# EMC03-Motion_Control.net
KiCad netlist of a schematic drawn in EAGLE
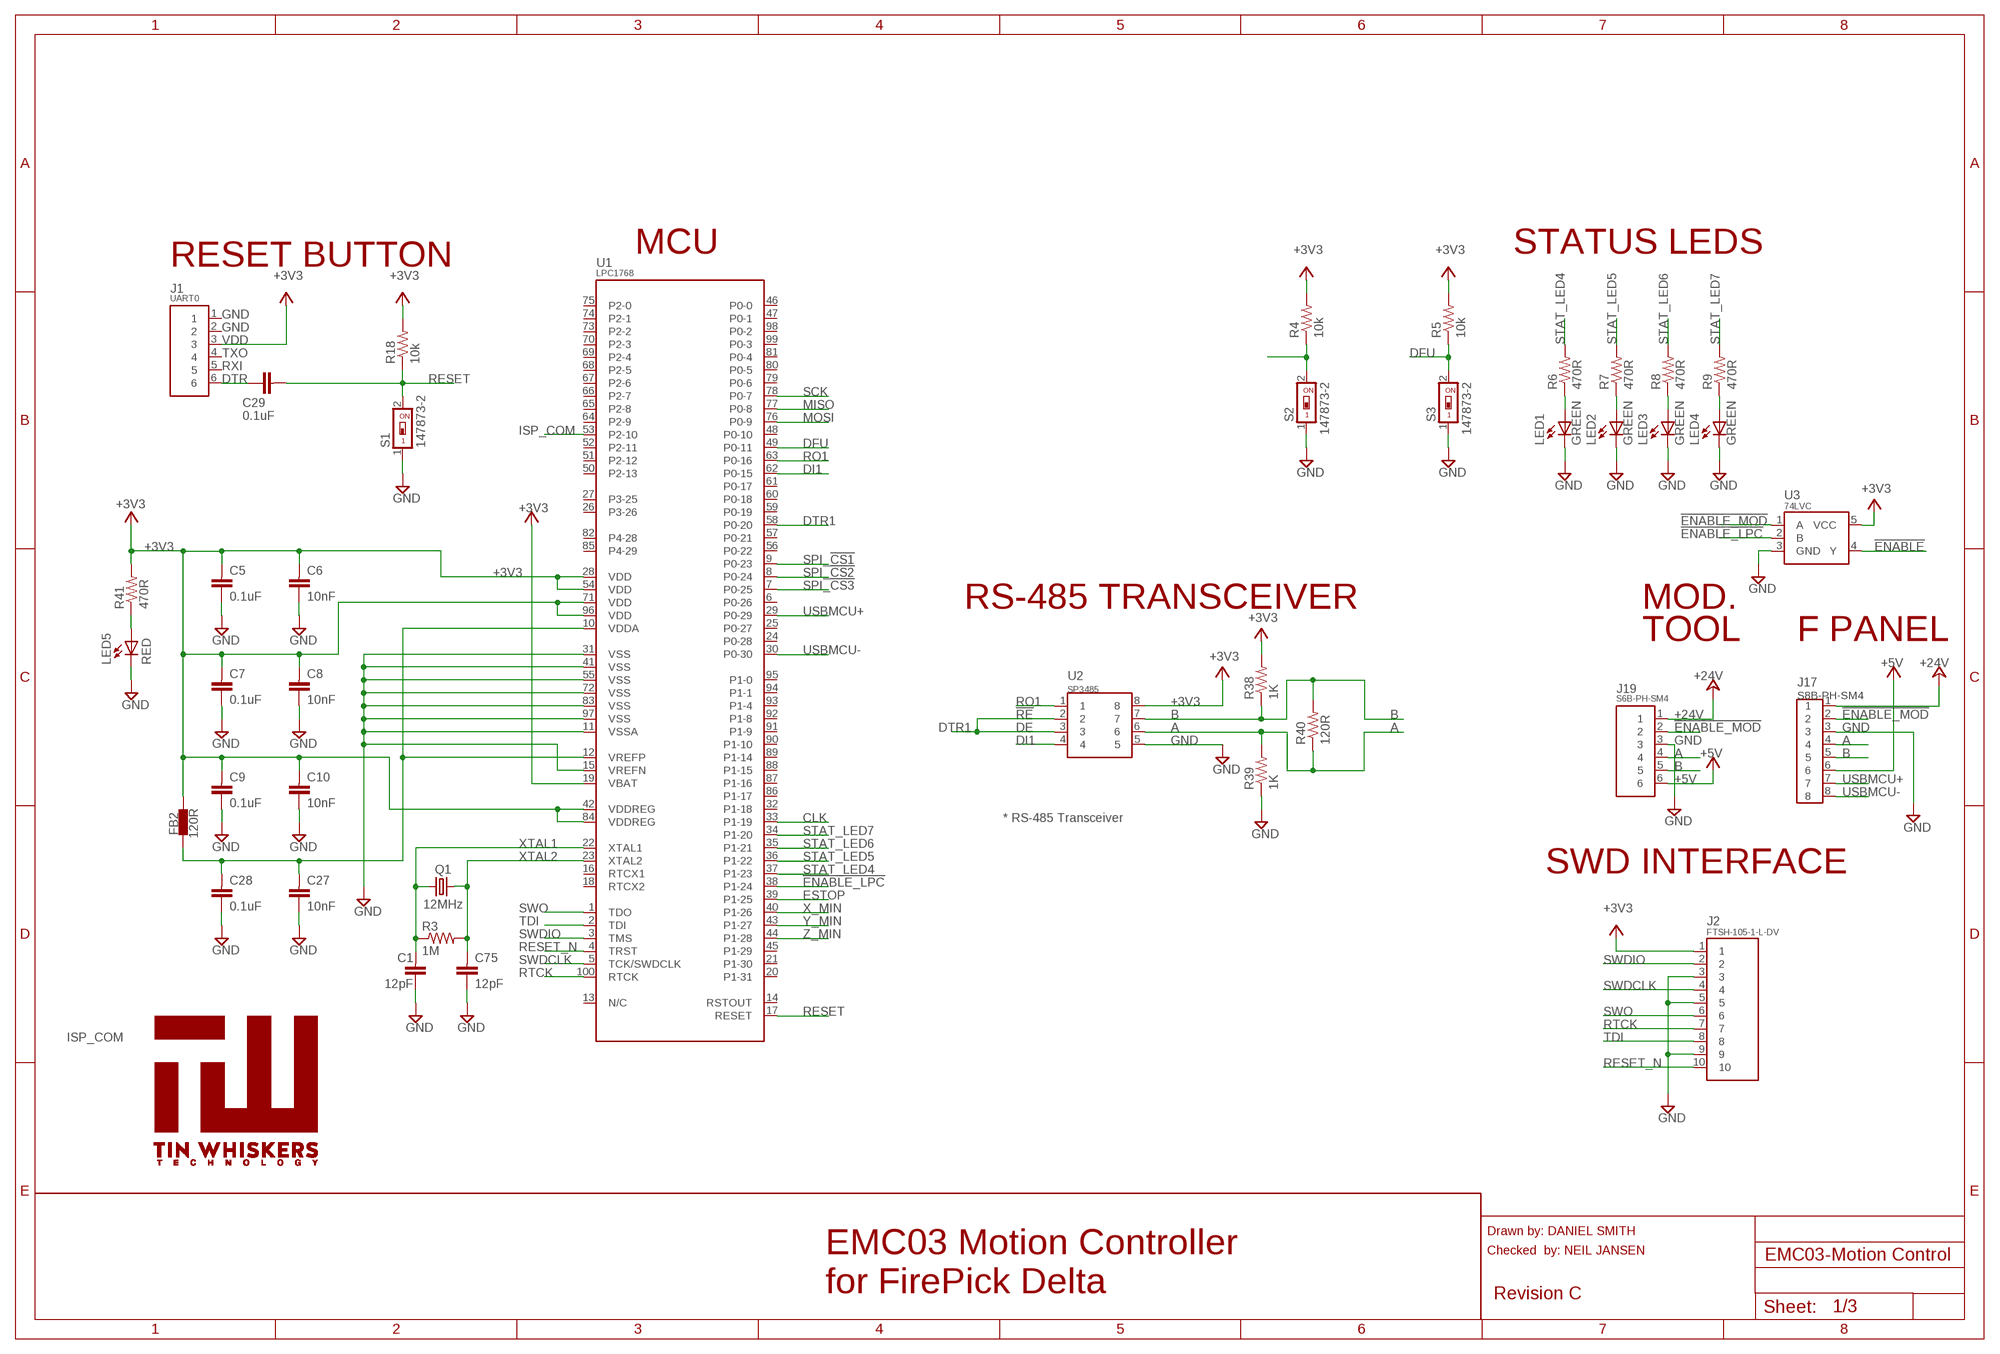
[diagram p0: schematic, sheet 1]
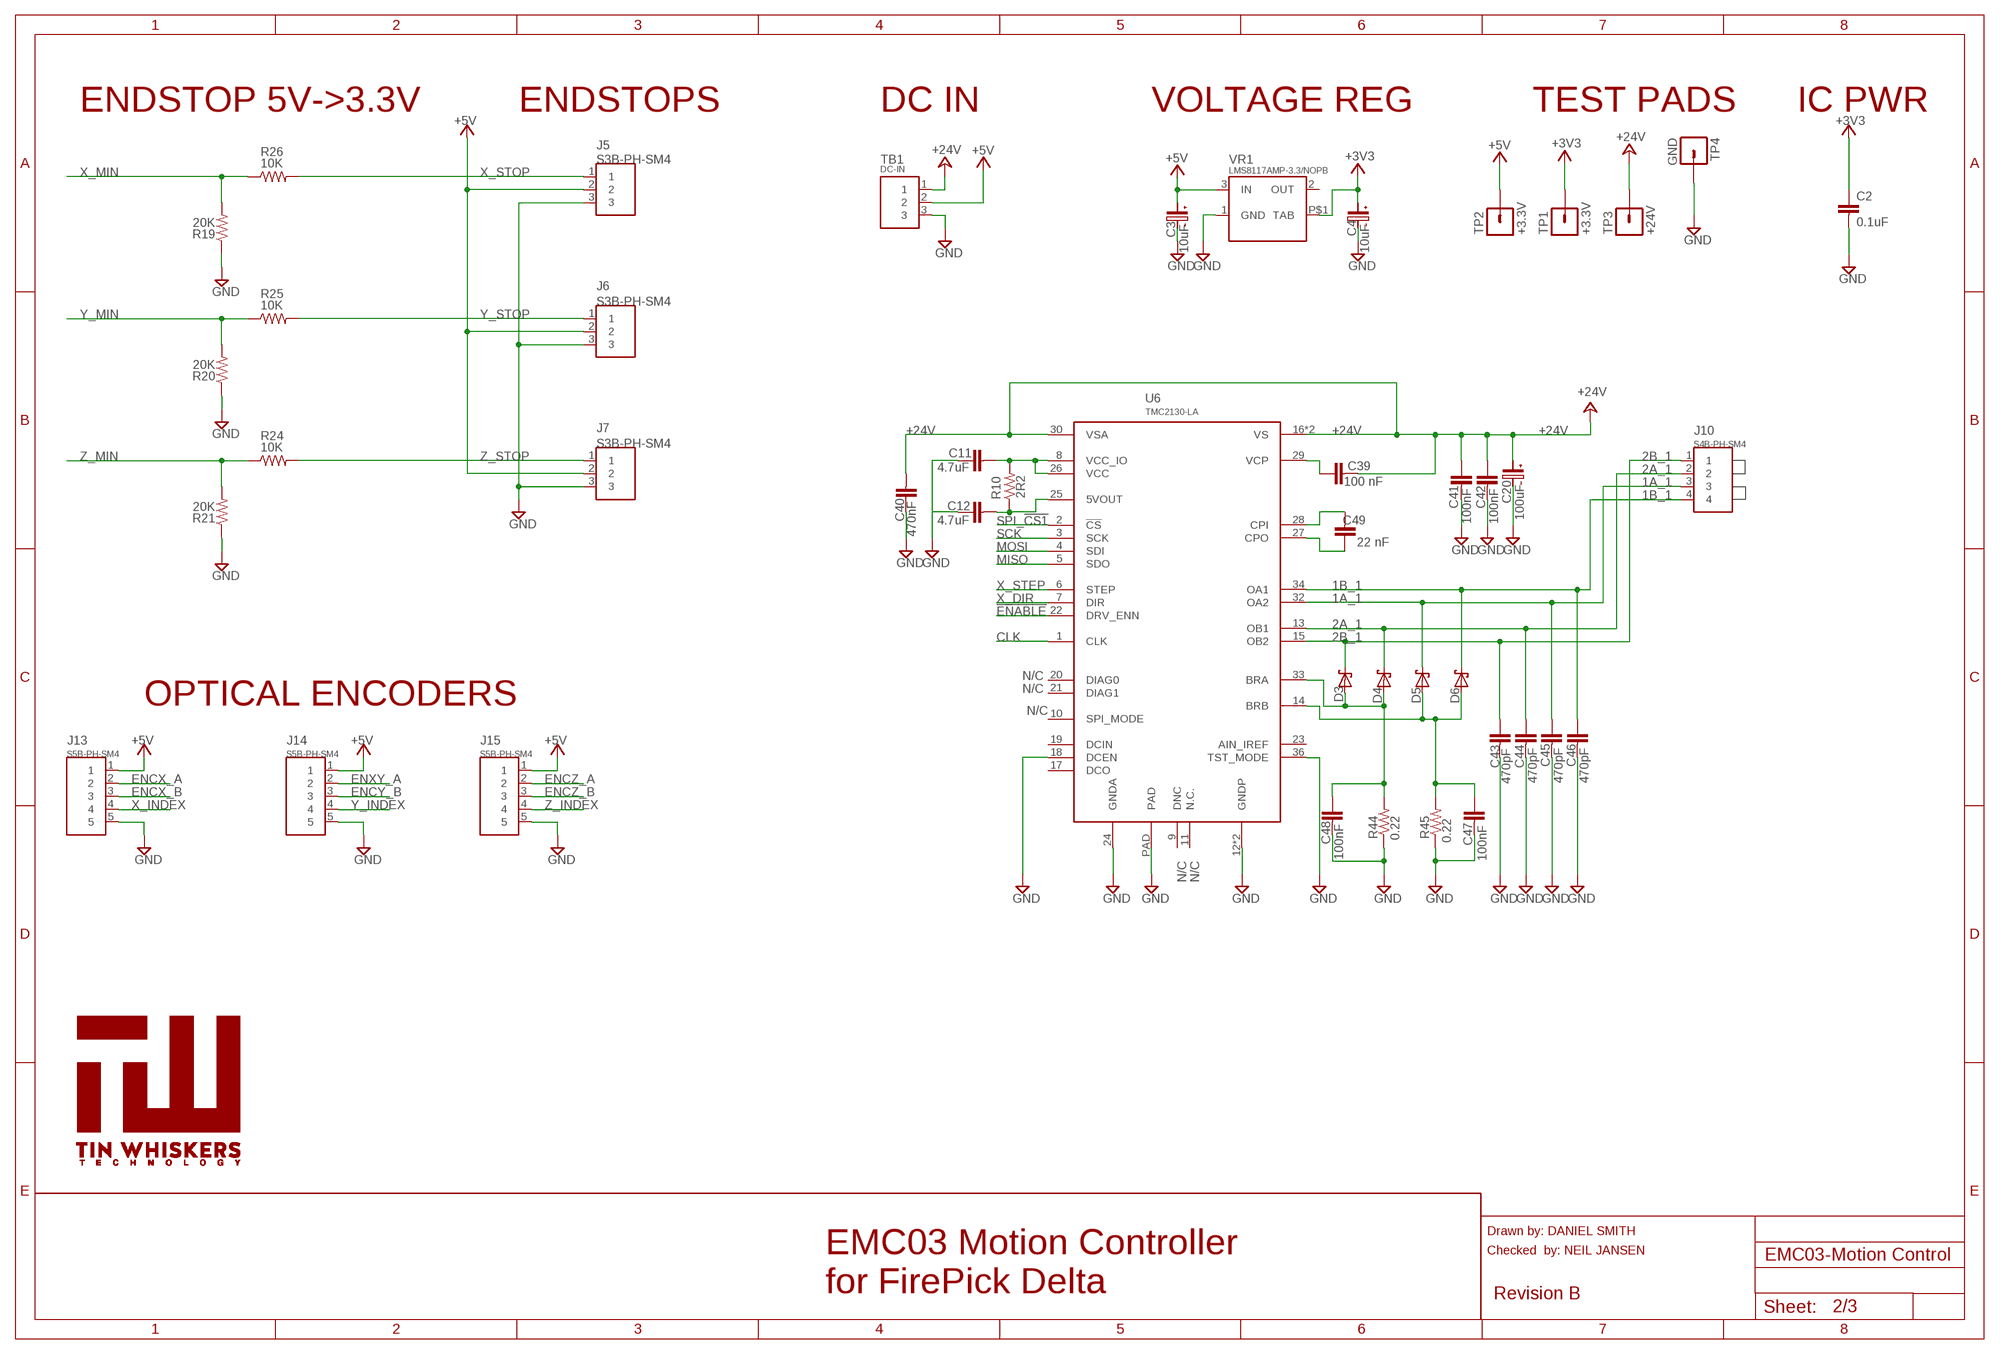
[diagram p1: schematic, sheet 2]
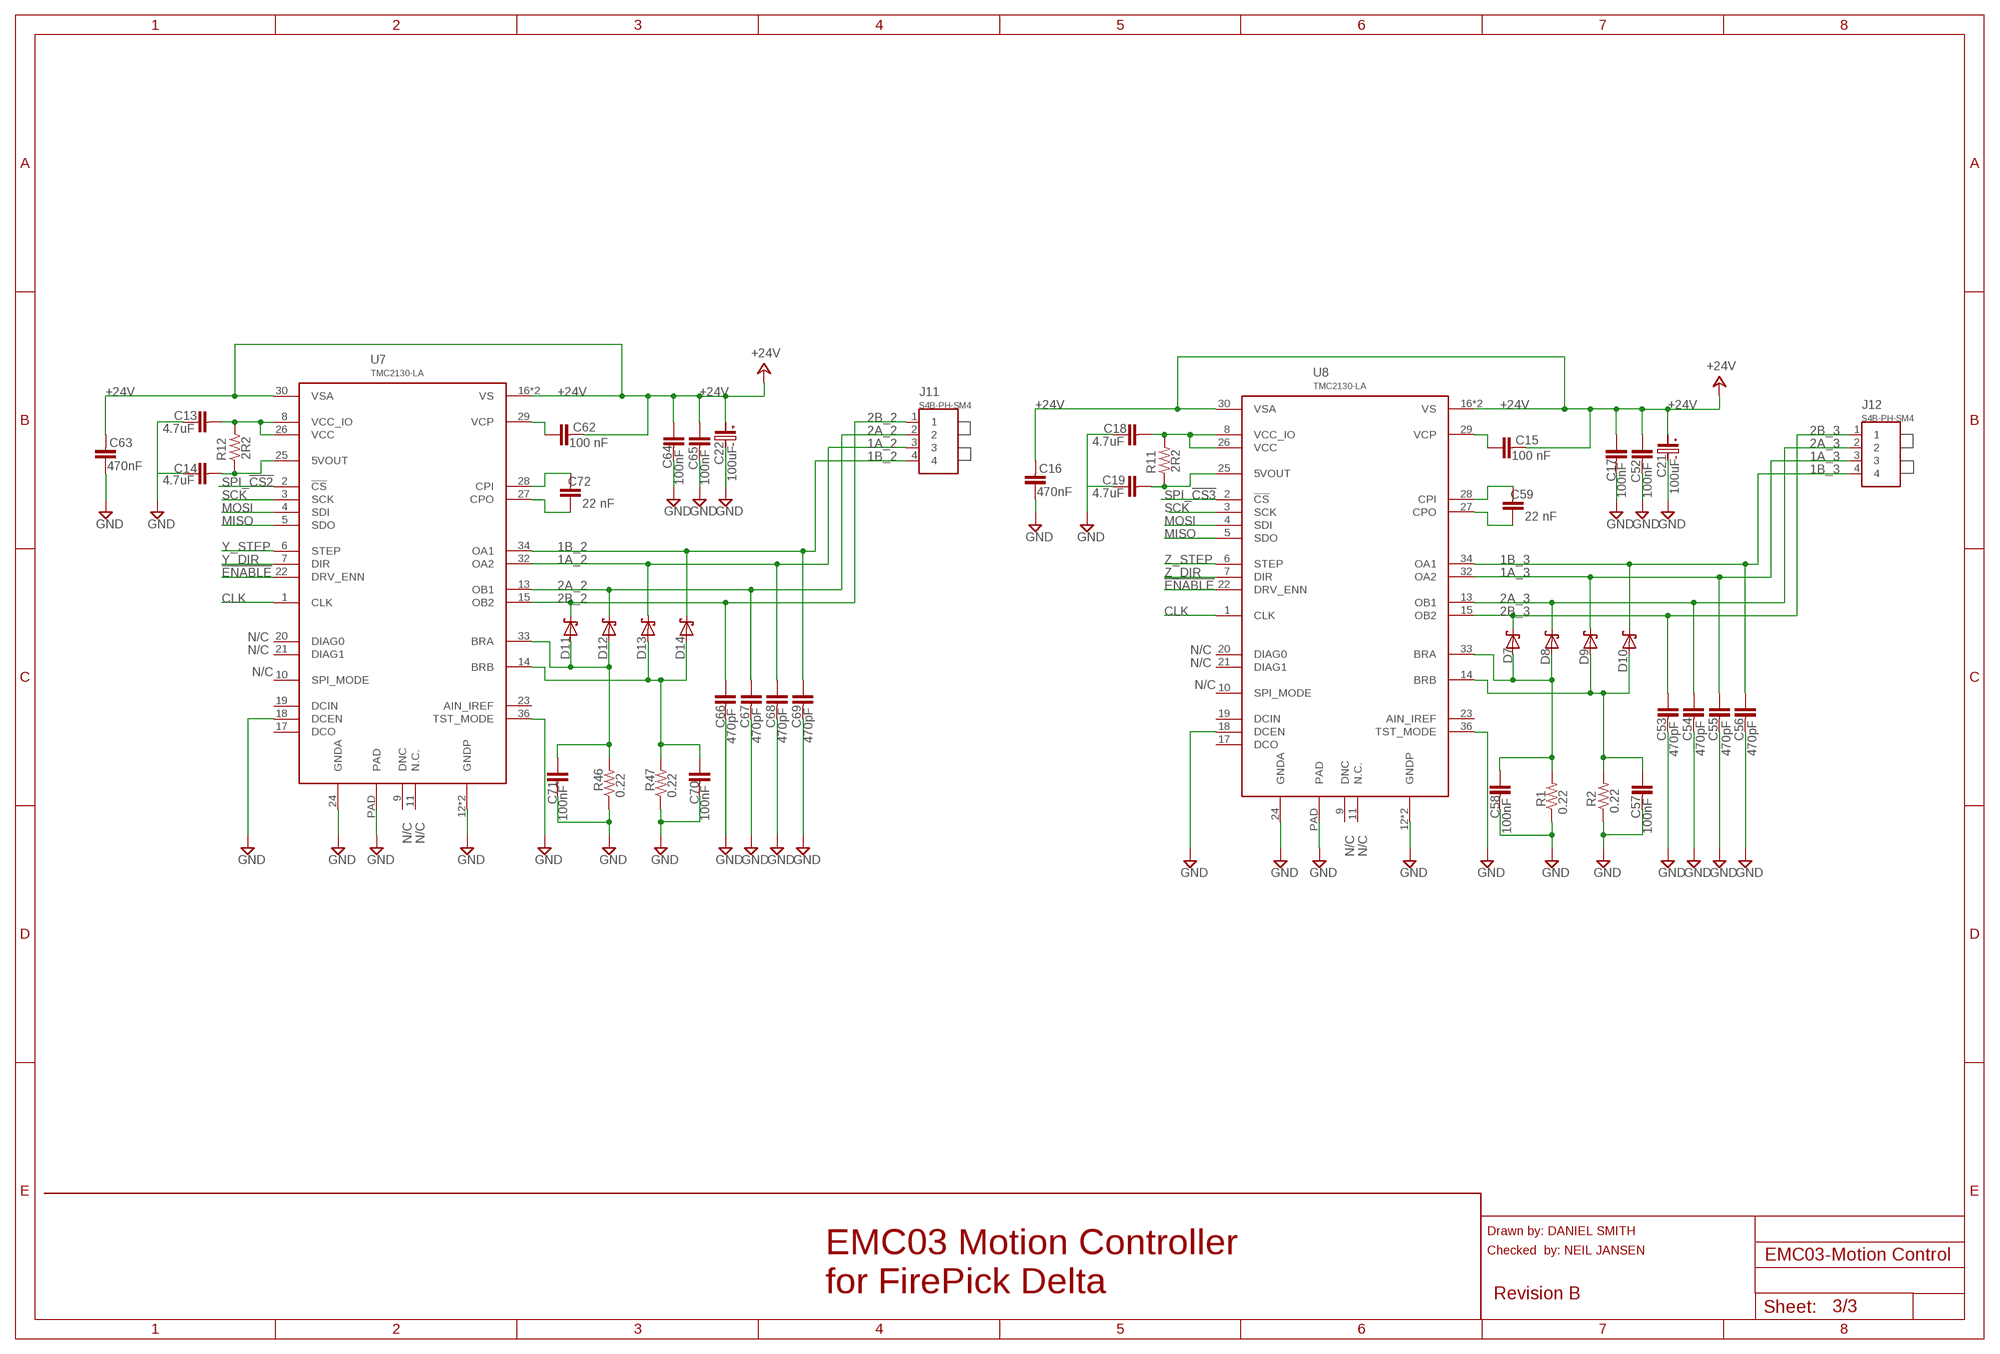
[diagram p2: schematic, sheet 3]

(export (version "E")
  (design (tool "Eeschema 10.0.6"))
  (components
    (comp (ref "C1")
      (value "12pF")
      (footprint "eagle-import:C0603")
      (fields (field (name "PARTNO") "GRM1885C1H120FA01J"))
      (libsource (lib "eagle-import") (part "CPL-CAP-C0G-0603-12PF-50V"))
    )
    (comp (ref "C5")
      (value "0.1uF")
      (footprint "eagle-import:C0603")
      (fields (field (name "PARTNO") "GMK107BJ104KAHT"))
      (libsource (lib "eagle-import") (part "CPL-CAP-X5R-0603-0.1UF-35V"))
    )
    (comp (ref "C6")
      (value "10nF")
      (footprint "eagle-import:C0603")
      (fields (field (name "PARTNO") "GRM188R71H103KA01D"))
      (libsource (lib "eagle-import") (part "CPL-CAP-X7R-10NF-16V"))
    )
    (comp (ref "C7")
      (value "0.1uF")
      (footprint "eagle-import:C0603")
      (fields (field (name "PARTNO") "GMK107BJ104KAHT"))
      (libsource (lib "eagle-import") (part "CPL-CAP-X5R-0603-0.1UF-35V"))
    )
    (comp (ref "C8")
      (value "10nF")
      (footprint "eagle-import:C0603")
      (fields (field (name "PARTNO") "GRM188R71H103KA01D"))
      (libsource (lib "eagle-import") (part "CPL-CAP-X7R-10NF-16V"))
    )
    (comp (ref "C9")
      (value "0.1uF")
      (footprint "eagle-import:C0603")
      (fields (field (name "PARTNO") "GMK107BJ104KAHT"))
      (libsource (lib "eagle-import") (part "CPL-CAP-X5R-0603-0.1UF-35V"))
    )
    (comp (ref "C10")
      (value "10nF")
      (footprint "eagle-import:C0603")
      (fields (field (name "PARTNO") "GRM188R71H103KA01D"))
      (libsource (lib "eagle-import") (part "CPL-CAP-X7R-10NF-16V"))
    )
    (comp (ref "C27")
      (value "10nF")
      (footprint "eagle-import:C0603")
      (fields (field (name "PARTNO") "GRM188R71H103KA01D"))
      (libsource (lib "eagle-import") (part "CPL-CAP-X7R-10NF-16V"))
    )
    (comp (ref "C28")
      (value "0.1uF")
      (footprint "eagle-import:C0603")
      (fields (field (name "PARTNO") "GMK107BJ104KAHT"))
      (libsource (lib "eagle-import") (part "CPL-CAP-X5R-0603-0.1UF-35V"))
    )
    (comp (ref "C29")
      (value "0.1uF")
      (footprint "eagle-import:C0603")
      (fields (field (name "PARTNO") "GMK107BJ104KAHT"))
      (libsource (lib "eagle-import") (part "CPL-CAP-X7R-0603-0.1UF-35V"))
    )
    (comp (ref "C75")
      (value "12pF")
      (footprint "eagle-import:C0603")
      (fields (field (name "PARTNO") "GRM1885C1H120FA01J"))
      (libsource (lib "eagle-import") (part "CPL-CAP-C0G-0603-12PF-50V"))
    )
    (comp (ref "FB2")
      (value "120R")
      (footprint "eagle-import:F0603")
      (fields (field (name "PARTNO") "BLM18AG121SN1D"))
      (libsource (lib "eagle-import") (part "CPL-IND-FER-120OHM-2A"))
    )
    (comp (ref "J1")
      (value "UART0")
      (footprint "eagle-import:CON-HDR-6POS-MALE")
      (fields (field (name "PARTNO") "67996-206HLF"))
      (libsource (lib "eagle-import") (part "CPL-CON-HEADER-0.1IN-6P-M"))
    )
    (comp (ref "J2")
      (value "FTSH-105-1-L-DV")
      (footprint "eagle-import:FTSH-105-01-XXX-DV-K")
      (fields (field (name "PARTNO") "FTSH-105-01-L-DV"))
      (libsource (lib "eagle-import") (part "CPL-CON-HEADER-0.05IN-10P-M"))
    )
    (comp (ref "J17")
      (value "S8B-PH-SM4")
      (footprint "eagle-import:CONN-JST-PH-2.0MM-8P-SMT-RA")
      (fields (field (name "PARTNO") "S8B-PH-SM4-TB(LF)(SN)"))
      (libsource (lib "eagle-import") (part "CPL-CON-JST-2.0MM-8P-M-RA"))
    )
    (comp (ref "J19")
      (value "S6B-PH-SM4")
      (footprint "eagle-import:CONN-JST-PH-2.0MM-6P-SMT-RA")
      (fields (field (name "PARTNO") "S6B-PH-SM4-TB(LF)(SN)"))
      (libsource (lib "eagle-import") (part "CPL-CON-JST-2.0MM-6P-M-RA"))
    )
    (comp (ref "LED1")
      (value "GREEN")
      (footprint "eagle-import:LED0603")
      (fields (field (name "PARTNO") "SML-D12M8WT86"))
      (libsource (lib "eagle-import") (part "CPL-LED-0603-GREEN"))
    )
    (comp (ref "LED2")
      (value "GREEN")
      (footprint "eagle-import:LED0603")
      (fields (field (name "PARTNO") "SML-D12M8WT86"))
      (libsource (lib "eagle-import") (part "CPL-LED-0603-GREEN"))
    )
    (comp (ref "LED3")
      (value "GREEN")
      (footprint "eagle-import:LED0603")
      (fields (field (name "PARTNO") "SML-D12M8WT86"))
      (libsource (lib "eagle-import") (part "CPL-LED-0603-GREEN"))
    )
    (comp (ref "LED4")
      (value "GREEN")
      (footprint "eagle-import:LED0603")
      (fields (field (name "PARTNO") "SML-D12M8WT86"))
      (libsource (lib "eagle-import") (part "CPL-LED-0603-GREEN"))
    )
    (comp (ref "LED5")
      (value "RED")
      (footprint "eagle-import:LED0603")
      (fields (field (name "PARTNO") "SML-D12U8WT86"))
      (libsource (lib "eagle-import") (part "CPL-LED-0603-RED"))
    )
    (comp (ref "Q1")
      (value "12MHz")
      (footprint "eagle-import:HC-49_U-S")
      (fields (field (name "PARTNO") "HCM4912000000ABJT"))
      (libsource (lib "eagle-import") (part "CPL-OSC-CRY-12MHZ-18PF"))
    )
    (comp (ref "R3")
      (value "1M")
      (footprint "eagle-import:R0603")
      (fields (field (name "PARTNO") "RC0603FR-071ML"))
      (libsource (lib "eagle-import") (part "CPL-RES-0603-1M-0.1W"))
    )
    (comp (ref "R4")
      (value "10k")
      (footprint "eagle-import:R0603")
      (fields (field (name "PARTNO") "RC0603FR-0710KL"))
      (libsource (lib "eagle-import") (part "CPL-RES-0603-10K-0.1W"))
    )
    (comp (ref "R5")
      (value "10k")
      (footprint "eagle-import:R0603")
      (fields (field (name "PARTNO") "RC0603FR-0710KL"))
      (libsource (lib "eagle-import") (part "CPL-RES-0603-10K-0.1W"))
    )
    (comp (ref "R6")
      (value "470R")
      (footprint "eagle-import:R0603")
      (fields (field (name "PARTNO") "RC0603FR-07470RL"))
      (libsource (lib "eagle-import") (part "CPL-RES-0603-470R-0.1W"))
    )
    (comp (ref "R7")
      (value "470R")
      (footprint "eagle-import:R0603")
      (fields (field (name "PARTNO") "RC0603FR-07470RL"))
      (libsource (lib "eagle-import") (part "CPL-RES-0603-470R-0.1W"))
    )
    (comp (ref "R8")
      (value "470R")
      (footprint "eagle-import:R0603")
      (fields (field (name "PARTNO") "RC0603FR-07470RL"))
      (libsource (lib "eagle-import") (part "CPL-RES-0603-470R-0.1W"))
    )
    (comp (ref "R9")
      (value "470R")
      (footprint "eagle-import:R0603")
      (fields (field (name "PARTNO") "RC0603FR-07470RL"))
      (libsource (lib "eagle-import") (part "CPL-RES-0603-470R-0.1W"))
    )
    (comp (ref "R18")
      (value "10k")
      (footprint "eagle-import:R0603")
      (fields (field (name "PARTNO") "RC0603FR-0710KL"))
      (libsource (lib "eagle-import") (part "CPL-RES-0603-10K-0.1W"))
    )
    (comp (ref "R38")
      (value "1K")
      (footprint "eagle-import:R0603")
      (fields (field (name "PARTNO") "RC0603FR-071KL"))
      (libsource (lib "eagle-import") (part "CPL-RES-0603-1K-0.1W"))
    )
    (comp (ref "R39")
      (value "1K")
      (footprint "eagle-import:R0603")
      (fields (field (name "PARTNO") "RC0603FR-071KL"))
      (libsource (lib "eagle-import") (part "CPL-RES-0603-1K-0.1W"))
    )
    (comp (ref "R40")
      (value "120R")
      (footprint "eagle-import:R0603")
      (fields (field (name "PARTNO") "RC0805FR-07120RL"))
      (libsource (lib "eagle-import") (part "CPL-RES-0603-120-0.1W"))
    )
    (comp (ref "R41")
      (value "470R")
      (footprint "eagle-import:R0603")
      (fields (field (name "PARTNO") "RC0603FR-07470RL"))
      (libsource (lib "eagle-import") (part "CPL-RES-0603-470R-0.1W"))
    )
    (comp (ref "S1")
      (value "147873-2")
      (footprint "eagle-import:147873-2")
      (libsource (lib "eagle-import") (part "CPL-SW-MOM-147873-2"))
    )
    (comp (ref "S2")
      (value "147873-2")
      (footprint "eagle-import:147873-2")
      (libsource (lib "eagle-import") (part "CPL-SW-MOM-147873-2"))
    )
    (comp (ref "S3")
      (value "147873-2")
      (footprint "eagle-import:147873-2")
      (libsource (lib "eagle-import") (part "CPL-SW-MOM-147873-2"))
    )
    (comp (ref "U$1")
      (value "TIN-WHISKERSSMALL")
      (footprint "eagle-import:TIN-WHISKERS-SMALL")
      (libsource (lib "eagle-import") (part "TIN-WHISKERSSMALL"))
    )
    (comp (ref "U1")
      (value "LPC1768")
      (footprint "eagle-import:100-LQFP")
      (libsource (lib "eagle-import") (part "LPC1768LQFP-100"))
    )
    (comp (ref "U2")
      (value "SP3485")
      (footprint "eagle-import:SOICN-8")
      (libsource (lib "eagle-import") (part "SP3485"))
    )
    (comp (ref "U3")
      (value "74LVC")
      (footprint "eagle-import:SOT-23-5")
      (fields (field (name "PARTNO") "SN74LVC1G32DBVR"))
      (libsource (lib "eagle-import") (part "CPL-IC-LOGIC-OR-1CH-74LVC"))
    )
    (comp (ref "C13")
      (value "4.7uF")
      (footprint "eagle-import:C0603")
      (fields (field (name "PARTNO") "GRM188C81E475KE11D"))
      (libsource (lib "eagle-import") (part "CPL-CAP-X5R-0603-4.7UF-10V"))
    )
    (comp (ref "C14")
      (value "4.7uF")
      (footprint "eagle-import:C0603")
      (fields (field (name "PARTNO") "GRM188C81E475KE11D"))
      (libsource (lib "eagle-import") (part "CPL-CAP-X5R-0603-4.7UF-10V"))
    )
    (comp (ref "C15")
      (value "100 nF")
      (footprint "eagle-import:C0603")
      (fields (field (name "PARTNO") "UMK107B7104KA-T"))
      (libsource (lib "eagle-import") (part "CPL-CAP-X7R-0603-100NF-100V"))
    )
    (comp (ref "C16")
      (value "470nF")
      (footprint "eagle-import:C0603")
      (fields (field (name "PARTNO") "UMK107B7474KA-TR"))
      (libsource (lib "eagle-import") (part "CPL-CAP-X7R-0603-0.47UF-35V"))
    )
    (comp (ref "C17")
      (value "100nF")
      (footprint "eagle-import:C0603")
      (fields (field (name "PARTNO") "UMK107B7104KA-T"))
      (libsource (lib "eagle-import") (part "CPL-CAP-X7R-0603-100NF-100V"))
    )
    (comp (ref "C18")
      (value "4.7uF")
      (footprint "eagle-import:C0603")
      (fields (field (name "PARTNO") "GRM188C81E475KE11D"))
      (libsource (lib "eagle-import") (part "CPL-CAP-X5R-0603-4.7UF-10V"))
    )
    (comp (ref "C19")
      (value "4.7uF")
      (footprint "eagle-import:C0603")
      (fields (field (name "PARTNO") "GRM188C81E475KE11D"))
      (libsource (lib "eagle-import") (part "CPL-CAP-X5R-0603-4.7UF-10V"))
    )
    (comp (ref "C21")
      (value "100uF")
      (footprint "eagle-import:C-SMD-6.3MM")
      (fields (field (name "PARTNO") "EEE-FTH101XAP"))
      (libsource (lib "eagle-import") (part "CPL-CAP-ALU-SMD-100UF-50V"))
    )
    (comp (ref "C22")
      (value "100uF")
      (footprint "eagle-import:C-SMD-6.3MM")
      (fields (field (name "PARTNO") "EEE-FTH101XAP"))
      (libsource (lib "eagle-import") (part "CPL-CAP-ALU-SMD-100UF-50V"))
    )
    (comp (ref "C52")
      (value "100nF")
      (footprint "eagle-import:C0603")
      (fields (field (name "PARTNO") "UMK107B7104KA-T"))
      (libsource (lib "eagle-import") (part "CPL-CAP-X7R-0603-100NF-100V"))
    )
    (comp (ref "C53")
      (value "470pF")
      (footprint "eagle-import:C0603")
      (fields (field (name "PARTNO") "GRM188R72A471KA01D"))
      (libsource (lib "eagle-import") (part "CPL-CAP-X7R-0603-470PF-100V"))
    )
    (comp (ref "C54")
      (value "470pF")
      (footprint "eagle-import:C0603")
      (fields (field (name "PARTNO") "GRM188R72A471KA01D"))
      (libsource (lib "eagle-import") (part "CPL-CAP-X7R-0603-470PF-100V"))
    )
    (comp (ref "C55")
      (value "470pF")
      (footprint "eagle-import:C0603")
      (fields (field (name "PARTNO") "GRM188R72A471KA01D"))
      (libsource (lib "eagle-import") (part "CPL-CAP-X7R-0603-470PF-100V"))
    )
    (comp (ref "C56")
      (value "470pF")
      (footprint "eagle-import:C0603")
      (fields (field (name "PARTNO") "GRM188R72A471KA01D"))
      (libsource (lib "eagle-import") (part "CPL-CAP-X7R-0603-470PF-100V"))
    )
    (comp (ref "C57")
      (value "100nF")
      (footprint "eagle-import:C0603")
      (fields (field (name "PARTNO") "UMK107B7104KA-T"))
      (libsource (lib "eagle-import") (part "CPL-CAP-X7R-0603-100NF-50V"))
    )
    (comp (ref "C58")
      (value "100nF")
      (footprint "eagle-import:C0603")
      (fields (field (name "PARTNO") "UMK107B7104KA-T"))
      (libsource (lib "eagle-import") (part "CPL-CAP-X7R-0603-100NF-50V"))
    )
    (comp (ref "C59")
      (value "22 nF")
      (footprint "eagle-import:C0603")
      (fields (field (name "PARTNO") "GRM188R71H223KA01D"))
      (libsource (lib "eagle-import") (part "CPL-CAP-X7R-0603-22NF-50V{dblquote}"))
    )
    (comp (ref "C62")
      (value "100 nF")
      (footprint "eagle-import:C0603")
      (fields (field (name "PARTNO") "UMK107B7104KA-T"))
      (libsource (lib "eagle-import") (part "CPL-CAP-X7R-0603-100NF-100V"))
    )
    (comp (ref "C63")
      (value "470nF")
      (footprint "eagle-import:C0603")
      (fields (field (name "PARTNO") "UMK107B7474KA-TR"))
      (libsource (lib "eagle-import") (part "CPL-CAP-X7R-0603-0.47UF-35V"))
    )
    (comp (ref "C64")
      (value "100nF")
      (footprint "eagle-import:C0603")
      (fields (field (name "PARTNO") "UMK107B7104KA-T"))
      (libsource (lib "eagle-import") (part "CPL-CAP-X7R-0603-100NF-100V"))
    )
    (comp (ref "C65")
      (value "100nF")
      (footprint "eagle-import:C0603")
      (fields (field (name "PARTNO") "UMK107B7104KA-T"))
      (libsource (lib "eagle-import") (part "CPL-CAP-X7R-0603-100NF-100V"))
    )
    (comp (ref "C66")
      (value "470pF")
      (footprint "eagle-import:C0603")
      (fields (field (name "PARTNO") "GRM188R72A471KA01D"))
      (libsource (lib "eagle-import") (part "CPL-CAP-X7R-0603-470PF-100V"))
    )
    (comp (ref "C67")
      (value "470pF")
      (footprint "eagle-import:C0603")
      (fields (field (name "PARTNO") "GRM188R72A471KA01D"))
      (libsource (lib "eagle-import") (part "CPL-CAP-X7R-0603-470PF-100V"))
    )
    (comp (ref "C68")
      (value "470pF")
      (footprint "eagle-import:C0603")
      (fields (field (name "PARTNO") "GRM188R72A471KA01D"))
      (libsource (lib "eagle-import") (part "CPL-CAP-X7R-0603-470PF-100V"))
    )
    (comp (ref "C69")
      (value "470pF")
      (footprint "eagle-import:C0603")
      (fields (field (name "PARTNO") "GRM188R72A471KA01D"))
      (libsource (lib "eagle-import") (part "CPL-CAP-X7R-0603-470PF-100V"))
    )
    (comp (ref "C70")
      (value "100nF")
      (footprint "eagle-import:C0603")
      (fields (field (name "PARTNO") "UMK107B7104KA-T"))
      (libsource (lib "eagle-import") (part "CPL-CAP-X7R-0603-100NF-50V"))
    )
    (comp (ref "C71")
      (value "100nF")
      (footprint "eagle-import:C0603")
      (fields (field (name "PARTNO") "UMK107B7104KA-T"))
      (libsource (lib "eagle-import") (part "CPL-CAP-X7R-0603-100NF-50V"))
    )
    (comp (ref "C72")
      (value "22 nF")
      (footprint "eagle-import:C0603")
      (fields (field (name "PARTNO") "GRM188R71H223KA01D"))
      (libsource (lib "eagle-import") (part "CPL-CAP-X7R-0603-22NF-50V{dblquote}"))
    )
    (comp (ref "D7")
      (value "MSS1P6")
      (footprint "eagle-import:MICRO-SMP")
      (libsource (lib "eagle-import") (part "CPL-DIO-MSS1P6-MICROSMP"))
    )
    (comp (ref "D8")
      (value "MSS1P6")
      (footprint "eagle-import:MICRO-SMP")
      (libsource (lib "eagle-import") (part "CPL-DIO-MSS1P6-MICROSMP"))
    )
    (comp (ref "D9")
      (value "MSS1P6")
      (footprint "eagle-import:MICRO-SMP")
      (libsource (lib "eagle-import") (part "CPL-DIO-MSS1P6-MICROSMP"))
    )
    (comp (ref "D10")
      (value "MSS1P6")
      (footprint "eagle-import:MICRO-SMP")
      (libsource (lib "eagle-import") (part "CPL-DIO-MSS1P6-MICROSMP"))
    )
    (comp (ref "D11")
      (value "MSS1P6")
      (footprint "eagle-import:MICRO-SMP")
      (libsource (lib "eagle-import") (part "CPL-DIO-MSS1P6-MICROSMP"))
    )
    (comp (ref "D12")
      (value "MSS1P6")
      (footprint "eagle-import:MICRO-SMP")
      (libsource (lib "eagle-import") (part "CPL-DIO-MSS1P6-MICROSMP"))
    )
    (comp (ref "D13")
      (value "MSS1P6")
      (footprint "eagle-import:MICRO-SMP")
      (libsource (lib "eagle-import") (part "CPL-DIO-MSS1P6-MICROSMP"))
    )
    (comp (ref "D14")
      (value "MSS1P6")
      (footprint "eagle-import:MICRO-SMP")
      (libsource (lib "eagle-import") (part "CPL-DIO-MSS1P6-MICROSMP"))
    )
    (comp (ref "J11")
      (value "S4B-PH-SM4")
      (footprint "eagle-import:CONN-JST-PH-2.0MM-4P-SMT-RA")
      (fields (field (name "PARTNO") "S4B-PH-SM4-TB(LF)(SN)"))
      (libsource (lib "eagle-import") (part "CPL-CON-JST-2.0MM-4P-M-RA"))
    )
    (comp (ref "J12")
      (value "S4B-PH-SM4")
      (footprint "eagle-import:CONN-JST-PH-2.0MM-4P-SMT-RA")
      (fields (field (name "PARTNO") "S4B-PH-SM4-TB(LF)(SN)"))
      (libsource (lib "eagle-import") (part "CPL-CON-JST-2.0MM-4P-M-RA"))
    )
    (comp (ref "R1")
      (value "0.22")
      (footprint "eagle-import:R1206")
      (fields (field (name "PARTNO") "RL1206FR-7W0R22L"))
      (libsource (lib "eagle-import") (part "CPL-RES-1206-0.22-0.5W"))
    )
    (comp (ref "R2")
      (value "0.22")
      (footprint "eagle-import:R1206")
      (fields (field (name "PARTNO") "RL1206FR-7W0R22L"))
      (libsource (lib "eagle-import") (part "CPL-RES-1206-0.22-0.5W"))
    )
    (comp (ref "R11")
      (value "2R2")
      (footprint "eagle-import:R0603")
      (fields (field (name "PARTNO") "RC0603FR-072R2L"))
      (libsource (lib "eagle-import") (part "CPL-RES-0603-2.2-0.1W"))
    )
    (comp (ref "R12")
      (value "2R2")
      (footprint "eagle-import:R0603")
      (fields (field (name "PARTNO") "RC0603FR-072R2L"))
      (libsource (lib "eagle-import") (part "CPL-RES-0603-2.2-0.1W"))
    )
    (comp (ref "R46")
      (value "0.22")
      (footprint "eagle-import:R1206")
      (fields (field (name "PARTNO") "RL1206FR-7W0R22L"))
      (libsource (lib "eagle-import") (part "CPL-RES-1206-0.22-0.5W"))
    )
    (comp (ref "R47")
      (value "0.22")
      (footprint "eagle-import:R1206")
      (fields (field (name "PARTNO") "RL1206FR-7W0R22L"))
      (libsource (lib "eagle-import") (part "CPL-RES-1206-0.22-0.5W"))
    )
    (comp (ref "U7")
      (value "TMC2130-LA")
      (footprint "eagle-import:36-QFN(5X6)")
      (libsource (lib "eagle-import") (part "CPL-MDR-2PHSTEPPER"))
    )
    (comp (ref "U8")
      (value "TMC2130-LA")
      (footprint "eagle-import:36-QFN(5X6)")
      (libsource (lib "eagle-import") (part "CPL-MDR-2PHSTEPPER"))
    )
    (comp (ref "C2")
      (value "0.1uF")
      (footprint "eagle-import:C0603")
      (fields (field (name "PARTNO") "UMK107B7104KA-T"))
      (libsource (lib "eagle-import") (part "CPL-CAP-X7R-0603-100NF-50V"))
    )
    (comp (ref "C3")
      (value "10uF")
      (footprint "eagle-import:C-SMD-6.3MM")
      (fields (field (name "PARTNO") "EMVH350ADA100MF60G"))
      (libsource (lib "eagle-import") (part "CPL-CAP-ALU-6.4MM-10UF-10V"))
    )
    (comp (ref "C4")
      (value "10uF")
      (footprint "eagle-import:C-SMD-6.3MM")
      (fields (field (name "PARTNO") "EMVH350ADA100MF60G"))
      (libsource (lib "eagle-import") (part "CPL-CAP-ALU-6.4MM-10UF-10V"))
    )
    (comp (ref "C11")
      (value "4.7uF")
      (footprint "eagle-import:C0603")
      (fields (field (name "PARTNO") "GRM188C81E475KE11D"))
      (libsource (lib "eagle-import") (part "CPL-CAP-X5R-0603-4.7UF-10V"))
    )
    (comp (ref "C12")
      (value "4.7uF")
      (footprint "eagle-import:C0603")
      (fields (field (name "PARTNO") "GRM188C81E475KE11D"))
      (libsource (lib "eagle-import") (part "CPL-CAP-X5R-0603-4.7UF-10V"))
    )
    (comp (ref "C20")
      (value "100uF")
      (footprint "eagle-import:C-SMD-6.3MM")
      (fields (field (name "PARTNO") "EEE-FTH101XAP"))
      (libsource (lib "eagle-import") (part "CPL-CAP-ALU-SMD-100UF-50V"))
    )
    (comp (ref "C39")
      (value "100 nF")
      (footprint "eagle-import:C0603")
      (fields (field (name "PARTNO") "UMK107B7104KA-T"))
      (libsource (lib "eagle-import") (part "CPL-CAP-X7R-0603-100NF-100V"))
    )
    (comp (ref "C40")
      (value "470nF")
      (footprint "eagle-import:C0603")
      (fields (field (name "PARTNO") "UMK107B7474KA-TR"))
      (libsource (lib "eagle-import") (part "CPL-CAP-X7R-0603-0.47UF-35V"))
    )
    (comp (ref "C41")
      (value "100nF")
      (footprint "eagle-import:C0603")
      (fields (field (name "PARTNO") "UMK107B7104KA-T"))
      (libsource (lib "eagle-import") (part "CPL-CAP-X7R-0603-100NF-100V"))
    )
    (comp (ref "C42")
      (value "100nF")
      (footprint "eagle-import:C0603")
      (fields (field (name "PARTNO") "UMK107B7104KA-T"))
      (libsource (lib "eagle-import") (part "CPL-CAP-X7R-0603-100NF-100V"))
    )
    (comp (ref "C43")
      (value "470pF")
      (footprint "eagle-import:C0603")
      (fields (field (name "PARTNO") "GRM188R72A471KA01D"))
      (libsource (lib "eagle-import") (part "CPL-CAP-X7R-0603-470PF-100V"))
    )
    (comp (ref "C44")
      (value "470pF")
      (footprint "eagle-import:C0603")
      (fields (field (name "PARTNO") "GRM188R72A471KA01D"))
      (libsource (lib "eagle-import") (part "CPL-CAP-X7R-0603-470PF-100V"))
    )
    (comp (ref "C45")
      (value "470pF")
      (footprint "eagle-import:C0603")
      (fields (field (name "PARTNO") "GRM188R72A471KA01D"))
      (libsource (lib "eagle-import") (part "CPL-CAP-X7R-0603-470PF-100V"))
    )
    (comp (ref "C46")
      (value "470pF")
      (footprint "eagle-import:C0603")
      (fields (field (name "PARTNO") "GRM188R72A471KA01D"))
      (libsource (lib "eagle-import") (part "CPL-CAP-X7R-0603-470PF-100V"))
    )
    (comp (ref "C47")
      (value "100nF")
      (footprint "eagle-import:C0603")
      (fields (field (name "PARTNO") "UMK107B7104KA-T"))
      (libsource (lib "eagle-import") (part "CPL-CAP-X7R-0603-100NF-50V"))
    )
    (comp (ref "C48")
      (value "100nF")
      (footprint "eagle-import:C0603")
      (fields (field (name "PARTNO") "UMK107B7104KA-T"))
      (libsource (lib "eagle-import") (part "CPL-CAP-X7R-0603-100NF-50V"))
    )
    (comp (ref "C49")
      (value "22 nF")
      (footprint "eagle-import:C0603")
      (fields (field (name "PARTNO") "GRM188R71H223KA01D"))
      (libsource (lib "eagle-import") (part "CPL-CAP-X7R-0603-22NF-50V{dblquote}"))
    )
    (comp (ref "D3")
      (value "MSS1P6")
      (footprint "eagle-import:MICRO-SMP")
      (libsource (lib "eagle-import") (part "CPL-DIO-MSS1P6-MICROSMP"))
    )
    (comp (ref "D4")
      (value "MSS1P6")
      (footprint "eagle-import:MICRO-SMP")
      (libsource (lib "eagle-import") (part "CPL-DIO-MSS1P6-MICROSMP"))
    )
    (comp (ref "D5")
      (value "MSS1P6")
      (footprint "eagle-import:MICRO-SMP")
      (libsource (lib "eagle-import") (part "CPL-DIO-MSS1P6-MICROSMP"))
    )
    (comp (ref "D6")
      (value "MSS1P6")
      (footprint "eagle-import:MICRO-SMP")
      (libsource (lib "eagle-import") (part "CPL-DIO-MSS1P6-MICROSMP"))
    )
    (comp (ref "J5")
      (value "S3B-PH-SM4")
      (footprint "eagle-import:CONN-JST-PH-2.0MM-3P-SMT-RA")
      (fields (field (name "PARTNO") "S3B-PH-SM4-TB(LF)(SN)"))
      (libsource (lib "eagle-import") (part "CPL-CON-JST-2.0MM-3P-M-RA"))
    )
    (comp (ref "J6")
      (value "S3B-PH-SM4")
      (footprint "eagle-import:CONN-JST-PH-2.0MM-3P-SMT-RA")
      (fields (field (name "PARTNO") "S3B-PH-SM4-TB(LF)(SN)"))
      (libsource (lib "eagle-import") (part "CPL-CON-JST-2.0MM-3P-M-RA"))
    )
    (comp (ref "J7")
      (value "S3B-PH-SM4")
      (footprint "eagle-import:CONN-JST-PH-2.0MM-3P-SMT-RA")
      (fields (field (name "PARTNO") "S3B-PH-SM4-TB(LF)(SN)"))
      (libsource (lib "eagle-import") (part "CPL-CON-JST-2.0MM-3P-M-RA"))
    )
    (comp (ref "J10")
      (value "S4B-PH-SM4")
      (footprint "eagle-import:CONN-JST-PH-2.0MM-4P-SMT-RA")
      (fields (field (name "PARTNO") "S4B-PH-SM4-TB(LF)(SN)"))
      (libsource (lib "eagle-import") (part "CPL-CON-JST-2.0MM-4P-M-RA"))
    )
    (comp (ref "J13")
      (value "S5B-PH-SM4")
      (footprint "eagle-import:CONN-JST-PH-2.0MM-5P-SMT-RA")
      (fields (field (name "PARTNO") "S5B-PH-SM4-TB(LF)(SN)"))
      (libsource (lib "eagle-import") (part "CPL-CON-JST-2.0MM-5P-M-RA"))
    )
    (comp (ref "J14")
      (value "S5B-PH-SM4")
      (footprint "eagle-import:CONN-JST-PH-2.0MM-5P-SMT-RA")
      (fields (field (name "PARTNO") "S5B-PH-SM4-TB(LF)(SN)"))
      (libsource (lib "eagle-import") (part "CPL-CON-JST-2.0MM-5P-M-RA"))
    )
    (comp (ref "J15")
      (value "S5B-PH-SM4")
      (footprint "eagle-import:CONN-JST-PH-2.0MM-5P-SMT-RA")
      (fields (field (name "PARTNO") "S5B-PH-SM4-TB(LF)(SN)"))
      (libsource (lib "eagle-import") (part "CPL-CON-JST-2.0MM-5P-M-RA"))
    )
    (comp (ref "R10")
      (value "2R2")
      (footprint "eagle-import:R0603")
      (fields (field (name "PARTNO") "RC0603FR-072R2L"))
      (libsource (lib "eagle-import") (part "CPL-RES-0603-2.2-0.1W"))
    )
    (comp (ref "R19")
      (value "20K")
      (footprint "eagle-import:R0603")
      (fields (field (name "PARTNO") "RC0603FR-0720KL"))
      (libsource (lib "eagle-import") (part "CPL-RES-0603-20K-0.1W"))
    )
    (comp (ref "R20")
      (value "20K")
      (footprint "eagle-import:R0603")
      (fields (field (name "PARTNO") "RC0603FR-0720KL"))
      (libsource (lib "eagle-import") (part "CPL-RES-0603-20K-0.1W"))
    )
    (comp (ref "R21")
      (value "20K")
      (footprint "eagle-import:R0603")
      (fields (field (name "PARTNO") "RC0603FR-0720KL"))
      (libsource (lib "eagle-import") (part "CPL-RES-0603-20K-0.1W"))
    )
    (comp (ref "R24")
      (value "10K")
      (footprint "eagle-import:R0603")
      (fields (field (name "PARTNO") "RC0603FR-0710KL"))
      (libsource (lib "eagle-import") (part "CPL-RES-0603-10K-0.1W"))
    )
    (comp (ref "R25")
      (value "10K")
      (footprint "eagle-import:R0603")
      (fields (field (name "PARTNO") "RC0603FR-0710KL"))
      (libsource (lib "eagle-import") (part "CPL-RES-0603-10K-0.1W"))
    )
    (comp (ref "R26")
      (value "10K")
      (footprint "eagle-import:R0603")
      (fields (field (name "PARTNO") "RC0603FR-0710KL"))
      (libsource (lib "eagle-import") (part "CPL-RES-0603-10K-0.1W"))
    )
    (comp (ref "R44")
      (value "0.22")
      (footprint "eagle-import:R1206")
      (fields (field (name "PARTNO") "RL1206FR-7W0R22L"))
      (libsource (lib "eagle-import") (part "CPL-RES-1206-0.22-0.5W"))
    )
    (comp (ref "R45")
      (value "0.22")
      (footprint "eagle-import:R1206")
      (fields (field (name "PARTNO") "RL1206FR-7W0R22L"))
      (libsource (lib "eagle-import") (part "CPL-RES-1206-0.22-0.5W"))
    )
    (comp (ref "TB1")
      (value "DC-IN")
      (footprint "eagle-import:TBLOCK-3-5MM-OSTTH030160")
      (fields (field (name "PARTNO") "OSTTH030160"))
      (libsource (lib "eagle-import") (part "CPL-TBLK-SCR-3CKT-5.0MM-OST"))
    )
    (comp (ref "TP1")
      (value "+3.3V")
      (footprint "eagle-import:TESTPAD")
      (libsource (lib "eagle-import") (part "TPAD"))
    )
    (comp (ref "TP2")
      (value "+3.3V")
      (footprint "eagle-import:TESTPAD")
      (libsource (lib "eagle-import") (part "TPAD"))
    )
    (comp (ref "TP3")
      (value "+24V")
      (footprint "eagle-import:TESTPAD")
      (libsource (lib "eagle-import") (part "TPAD"))
    )
    (comp (ref "TP4")
      (value "GND")
      (footprint "eagle-import:TESTPAD")
      (libsource (lib "eagle-import") (part "TPAD"))
    )
    (comp (ref "U$2")
      (value "TIN-WHISKERSSMALL")
      (footprint "eagle-import:TIN-WHISKERS-SMALL")
      (libsource (lib "eagle-import") (part "TIN-WHISKERSSMALL"))
    )
    (comp (ref "U6")
      (value "TMC2130-LA")
      (footprint "eagle-import:36-QFN(5X6)")
      (libsource (lib "eagle-import") (part "CPL-MDR-2PHSTEPPER"))
    )
    (comp (ref "VR1")
      (value "LMS8117AMP-3.3/NOPB")
      (footprint "eagle-import:SOT-223")
      (libsource (lib "eagle-import") (part "CPL-REG-LIN-3.3V-1A"))
    )
  )
  (nets
    (net (code "1") (name "+3V3") (class "Default")
      (node (ref "C10") (pin "2") (pinfunction "2_2") (pintype "passive"))
      (node (ref "C2") (pin "1") (pinfunction "1_1") (pintype "passive"))
      (node (ref "C4") (pin "POS") (pinfunction "POS_POS") (pintype "passive"))
      (node (ref "C5") (pin "2") (pinfunction "2_2") (pintype "passive"))
      (node (ref "C6") (pin "2") (pinfunction "2_2") (pintype "passive"))
      (node (ref "C7") (pin "2") (pinfunction "2_2") (pintype "passive"))
      (node (ref "C8") (pin "2") (pinfunction "2_2") (pintype "passive"))
      (node (ref "C9") (pin "2") (pinfunction "2_2") (pintype "passive"))
      (node (ref "FB2") (pin "2") (pinfunction "2_2") (pintype "passive"))
      (node (ref "J1") (pin "3") (pinfunction "3_3") (pintype "bidirectional"))
      (node (ref "J2") (pin "1") (pinfunction "1_1") (pintype "bidirectional"))
      (node (ref "R18") (pin "2") (pinfunction "2_2") (pintype "passive"))
      (node (ref "R38") (pin "2") (pinfunction "2_2") (pintype "passive"))
      (node (ref "R4") (pin "2") (pinfunction "2_2") (pintype "passive"))
      (node (ref "R41") (pin "2") (pinfunction "2_2") (pintype "passive"))
      (node (ref "R5") (pin "2") (pinfunction "2_2") (pintype "passive"))
      (node (ref "TP1") (pin "PAD") (pinfunction "2_PAD") (pintype "passive"))
      (node (ref "U1") (pin "19") (pinfunction "VBAT_19") (pintype "power_in"))
      (node (ref "U1") (pin "28") (pinfunction "VDD_28") (pintype "power_in"))
      (node (ref "U1") (pin "42") (pinfunction "VDDREG_42") (pintype "power_in"))
      (node (ref "U1") (pin "54") (pinfunction "VDD_54") (pintype "power_in"))
      (node (ref "U1") (pin "71") (pinfunction "VDD_71") (pintype "power_in"))
      (node (ref "U1") (pin "84") (pinfunction "VDDREG_84") (pintype "power_in"))
      (node (ref "U1") (pin "96") (pinfunction "VDD_96") (pintype "power_in"))
      (node (ref "U2") (pin "8") (pinfunction "8_8") (pintype "bidirectional"))
      (node (ref "U3") (pin "5") (pinfunction "VCC_5") (pintype "bidirectional"))
      (node (ref "VR1") (pin "P$1") (pinfunction "TAB_P$1") (pintype "bidirectional"))
    )
    (net (code "2") (name "+5V") (class "Default")
      (node (ref "C3") (pin "POS") (pinfunction "POS_POS") (pintype "passive"))
      (node (ref "J13") (pin "1") (pinfunction "1_1") (pintype "bidirectional"))
      (node (ref "J14") (pin "1") (pinfunction "1_1") (pintype "bidirectional"))
      (node (ref "J15") (pin "1") (pinfunction "1_1") (pintype "bidirectional"))
      (node (ref "J17") (pin "6") (pinfunction "6_6") (pintype "passive"))
      (node (ref "J19") (pin "6") (pinfunction "6_6") (pintype "bidirectional"))
      (node (ref "J5") (pin "2") (pinfunction "2_2") (pintype "passive"))
      (node (ref "J6") (pin "2") (pinfunction "2_2") (pintype "passive"))
      (node (ref "J7") (pin "2") (pinfunction "2_2") (pintype "passive"))
      (node (ref "TB1") (pin "2") (pinfunction "2_2") (pintype "passive"))
      (node (ref "TP2") (pin "PAD") (pinfunction "2_PAD") (pintype "passive"))
      (node (ref "VR1") (pin "3") (pinfunction "IN_3") (pintype "bidirectional"))
    )
    (net (code "3") (name "+24V") (class "Default")
      (node (ref "C15") (pin "2") (pinfunction "2_2") (pintype "passive"))
      (node (ref "C16") (pin "2") (pinfunction "2_2") (pintype "passive"))
      (node (ref "C17") (pin "1") (pinfunction "1_1") (pintype "passive"))
      (node (ref "C20") (pin "POS") (pinfunction "POS_POS") (pintype "passive"))
      (node (ref "C21") (pin "POS") (pinfunction "POS_POS") (pintype "passive"))
      (node (ref "C22") (pin "POS") (pinfunction "POS_POS") (pintype "passive"))
      (node (ref "C39") (pin "2") (pinfunction "2_2") (pintype "passive"))
      (node (ref "C40") (pin "2") (pinfunction "2_2") (pintype "passive"))
      (node (ref "C41") (pin "1") (pinfunction "1_1") (pintype "passive"))
      (node (ref "C42") (pin "1") (pinfunction "1_1") (pintype "passive"))
      (node (ref "C52") (pin "1") (pinfunction "1_1") (pintype "passive"))
      (node (ref "C62") (pin "2") (pinfunction "2_2") (pintype "passive"))
      (node (ref "C63") (pin "2") (pinfunction "2_2") (pintype "passive"))
      (node (ref "C64") (pin "1") (pinfunction "1_1") (pintype "passive"))
      (node (ref "C65") (pin "1") (pinfunction "1_1") (pintype "passive"))
      (node (ref "J17") (pin "1") (pinfunction "1_1") (pintype "passive"))
      (node (ref "J19") (pin "1") (pinfunction "1_1") (pintype "bidirectional"))
      (node (ref "TB1") (pin "1") (pinfunction "1_1") (pintype "passive"))
      (node (ref "TP3") (pin "PAD") (pinfunction "2_PAD") (pintype "passive"))
      (node (ref "U6") (pin "16") (pinfunction "VS_16") (pintype "bidirectional"))
      (node (ref "U6") (pin "30") (pinfunction "VSA_30") (pintype "bidirectional"))
      (node (ref "U6") (pin "31") (pinfunction "VS_31") (pintype "bidirectional"))
      (node (ref "U7") (pin "16") (pinfunction "VS_16") (pintype "bidirectional"))
      (node (ref "U7") (pin "30") (pinfunction "VSA_30") (pintype "bidirectional"))
      (node (ref "U7") (pin "31") (pinfunction "VS_31") (pintype "bidirectional"))
      (node (ref "U8") (pin "16") (pinfunction "VS_16") (pintype "bidirectional"))
      (node (ref "U8") (pin "30") (pinfunction "VSA_30") (pintype "bidirectional"))
      (node (ref "U8") (pin "31") (pinfunction "VS_31") (pintype "bidirectional"))
    )
    (net (code "4") (name "1A_1") (class "Default")
      (node (ref "C45") (pin "1") (pinfunction "1_1") (pintype "passive"))
      (node (ref "D5") (pin "NEG") (pinfunction "C_NEG") (pintype "passive"))
      (node (ref "J10") (pin "3") (pinfunction "3_3") (pintype "passive"))
      (node (ref "U6") (pin "32") (pinfunction "OA2_32") (pintype "bidirectional"))
    )
    (net (code "5") (name "1A_2") (class "Default")
      (node (ref "C68") (pin "1") (pinfunction "1_1") (pintype "passive"))
      (node (ref "D13") (pin "NEG") (pinfunction "C_NEG") (pintype "passive"))
      (node (ref "J11") (pin "3") (pinfunction "3_3") (pintype "passive"))
      (node (ref "U7") (pin "32") (pinfunction "OA2_32") (pintype "bidirectional"))
    )
    (net (code "6") (name "1A_3") (class "Default")
      (node (ref "C55") (pin "1") (pinfunction "1_1") (pintype "passive"))
      (node (ref "D9") (pin "NEG") (pinfunction "C_NEG") (pintype "passive"))
      (node (ref "J12") (pin "3") (pinfunction "3_3") (pintype "passive"))
      (node (ref "U8") (pin "32") (pinfunction "OA2_32") (pintype "bidirectional"))
    )
    (net (code "7") (name "1B_1") (class "Default")
      (node (ref "C46") (pin "1") (pinfunction "1_1") (pintype "passive"))
      (node (ref "D6") (pin "NEG") (pinfunction "C_NEG") (pintype "passive"))
      (node (ref "J10") (pin "4") (pinfunction "4_4") (pintype "passive"))
      (node (ref "U6") (pin "34") (pinfunction "OA1_34") (pintype "bidirectional"))
    )
    (net (code "8") (name "1B_2") (class "Default")
      (node (ref "C69") (pin "1") (pinfunction "1_1") (pintype "passive"))
      (node (ref "D14") (pin "NEG") (pinfunction "C_NEG") (pintype "passive"))
      (node (ref "J11") (pin "4") (pinfunction "4_4") (pintype "passive"))
      (node (ref "U7") (pin "34") (pinfunction "OA1_34") (pintype "bidirectional"))
    )
    (net (code "9") (name "1B_3") (class "Default")
      (node (ref "C56") (pin "1") (pinfunction "1_1") (pintype "passive"))
      (node (ref "D10") (pin "NEG") (pinfunction "C_NEG") (pintype "passive"))
      (node (ref "J12") (pin "4") (pinfunction "4_4") (pintype "passive"))
      (node (ref "U8") (pin "34") (pinfunction "OA1_34") (pintype "bidirectional"))
    )
    (net (code "10") (name "2A_1") (class "Default")
      (node (ref "C44") (pin "1") (pinfunction "1_1") (pintype "passive"))
      (node (ref "D4") (pin "NEG") (pinfunction "C_NEG") (pintype "passive"))
      (node (ref "J10") (pin "2") (pinfunction "2_2") (pintype "passive"))
      (node (ref "U6") (pin "13") (pinfunction "OB1_13") (pintype "bidirectional"))
    )
    (net (code "11") (name "2A_2") (class "Default")
      (node (ref "C67") (pin "1") (pinfunction "1_1") (pintype "passive"))
      (node (ref "D12") (pin "NEG") (pinfunction "C_NEG") (pintype "passive"))
      (node (ref "J11") (pin "2") (pinfunction "2_2") (pintype "passive"))
      (node (ref "U7") (pin "13") (pinfunction "OB1_13") (pintype "bidirectional"))
    )
    (net (code "12") (name "2A_3") (class "Default")
      (node (ref "C54") (pin "1") (pinfunction "1_1") (pintype "passive"))
      (node (ref "D8") (pin "NEG") (pinfunction "C_NEG") (pintype "passive"))
      (node (ref "J12") (pin "2") (pinfunction "2_2") (pintype "passive"))
      (node (ref "U8") (pin "13") (pinfunction "OB1_13") (pintype "bidirectional"))
    )
    (net (code "13") (name "2B_1") (class "Default")
      (node (ref "C43") (pin "1") (pinfunction "1_1") (pintype "passive"))
      (node (ref "D3") (pin "NEG") (pinfunction "C_NEG") (pintype "passive"))
      (node (ref "J10") (pin "1") (pinfunction "1_1") (pintype "passive"))
      (node (ref "U6") (pin "15") (pinfunction "OB2_15") (pintype "bidirectional"))
    )
    (net (code "14") (name "2B_2") (class "Default")
      (node (ref "C66") (pin "1") (pinfunction "1_1") (pintype "passive"))
      (node (ref "D11") (pin "NEG") (pinfunction "C_NEG") (pintype "passive"))
      (node (ref "J11") (pin "1") (pinfunction "1_1") (pintype "passive"))
      (node (ref "U7") (pin "15") (pinfunction "OB2_15") (pintype "bidirectional"))
    )
    (net (code "15") (name "2B_3") (class "Default")
      (node (ref "C53") (pin "1") (pinfunction "1_1") (pintype "passive"))
      (node (ref "D7") (pin "NEG") (pinfunction "C_NEG") (pintype "passive"))
      (node (ref "J12") (pin "1") (pinfunction "1_1") (pintype "passive"))
      (node (ref "U8") (pin "15") (pinfunction "OB2_15") (pintype "bidirectional"))
    )
    (net (code "16") (name "A") (class "Default")
      (node (ref "J17") (pin "4") (pinfunction "4_4") (pintype "passive"))
      (node (ref "J19") (pin "4") (pinfunction "4_4") (pintype "bidirectional"))
      (node (ref "R39") (pin "2") (pinfunction "2_2") (pintype "passive"))
      (node (ref "R40") (pin "1") (pinfunction "1_1") (pintype "passive"))
      (node (ref "U2") (pin "6") (pinfunction "6_6") (pintype "bidirectional"))
    )
    (net (code "17") (name "B") (class "Default")
      (node (ref "J17") (pin "5") (pinfunction "5_5") (pintype "passive"))
      (node (ref "J19") (pin "5") (pinfunction "5_5") (pintype "bidirectional"))
      (node (ref "R38") (pin "1") (pinfunction "1_1") (pintype "passive"))
      (node (ref "R40") (pin "2") (pinfunction "2_2") (pintype "passive"))
      (node (ref "U2") (pin "7") (pinfunction "7_7") (pintype "bidirectional"))
    )
    (net (code "18") (name "CLK") (class "Default")
      (node (ref "U1") (pin "33") (pinfunction "P1-19_33") (pintype "bidirectional"))
      (node (ref "U6") (pin "1") (pinfunction "CLK_1") (pintype "bidirectional"))
      (node (ref "U7") (pin "1") (pinfunction "CLK_1") (pintype "bidirectional"))
      (node (ref "U8") (pin "1") (pinfunction "CLK_1") (pintype "bidirectional"))
    )
    (net (code "19") (name "DFU") (class "Default")
      (node (ref "R5") (pin "1") (pinfunction "1_1") (pintype "passive"))
      (node (ref "S3") (pin "2") (pinfunction "2_2") (pintype "passive"))
      (node (ref "U1") (pin "49") (pinfunction "P0-11_49") (pintype "bidirectional"))
    )
    (net (code "20") (name "DI1") (class "Default")
      (node (ref "U1") (pin "62") (pinfunction "P0-15_62") (pintype "bidirectional"))
      (node (ref "U2") (pin "4") (pinfunction "4_4") (pintype "bidirectional"))
    )
    (net (code "21") (name "DTR") (class "Default")
      (node (ref "C29") (pin "1") (pinfunction "1_1") (pintype "passive"))
      (node (ref "J1") (pin "6") (pinfunction "6_6") (pintype "bidirectional"))
    )
    (net (code "22") (name "DTR1") (class "Default")
      (node (ref "U1") (pin "58") (pinfunction "P0-20_58") (pintype "bidirectional"))
      (node (ref "U2") (pin "2") (pinfunction "2_2") (pintype "bidirectional"))
      (node (ref "U2") (pin "3") (pinfunction "3_3") (pintype "bidirectional"))
    )
    (net (code "23") (name "ENCX_A") (class "Default")
      (node (ref "J13") (pin "2") (pinfunction "2_2") (pintype "bidirectional"))
    )
    (net (code "24") (name "ENCX_B") (class "Default")
      (node (ref "J13") (pin "3") (pinfunction "3_3") (pintype "bidirectional"))
    )
    (net (code "25") (name "ENCY_B") (class "Default")
      (node (ref "J14") (pin "3") (pinfunction "3_3") (pintype "bidirectional"))
    )
    (net (code "26") (name "ENCZ_A") (class "Default")
      (node (ref "J15") (pin "2") (pinfunction "2_2") (pintype "bidirectional"))
    )
    (net (code "27") (name "ENCZ_B") (class "Default")
      (node (ref "J15") (pin "3") (pinfunction "3_3") (pintype "bidirectional"))
    )
    (net (code "28") (name "ENXY_A") (class "Default")
      (node (ref "J14") (pin "2") (pinfunction "2_2") (pintype "bidirectional"))
    )
    (net (code "29") (name "ESTOP") (class "Default")
      (node (ref "U1") (pin "39") (pinfunction "P1-25_39") (pintype "bidirectional"))
    )
    (net (code "30") (name "GND") (class "Default")
      (node (ref "C1") (pin "1") (pinfunction "1_1") (pintype "passive"))
      (node (ref "C10") (pin "1") (pinfunction "1_1") (pintype "passive"))
      (node (ref "C11") (pin "1") (pinfunction "1_1") (pintype "passive"))
      (node (ref "C12") (pin "1") (pinfunction "1_1") (pintype "passive"))
      (node (ref "C13") (pin "1") (pinfunction "1_1") (pintype "passive"))
      (node (ref "C14") (pin "1") (pinfunction "1_1") (pintype "passive"))
      (node (ref "C16") (pin "1") (pinfunction "1_1") (pintype "passive"))
      (node (ref "C17") (pin "2") (pinfunction "2_2") (pintype "passive"))
      (node (ref "C18") (pin "1") (pinfunction "1_1") (pintype "passive"))
      (node (ref "C19") (pin "1") (pinfunction "1_1") (pintype "passive"))
      (node (ref "C2") (pin "2") (pinfunction "2_2") (pintype "passive"))
      (node (ref "C20") (pin "NEG") (pinfunction "NEG_NEG") (pintype "passive"))
      (node (ref "C21") (pin "NEG") (pinfunction "NEG_NEG") (pintype "passive"))
      (node (ref "C22") (pin "NEG") (pinfunction "NEG_NEG") (pintype "passive"))
      (node (ref "C27") (pin "1") (pinfunction "1_1") (pintype "passive"))
      (node (ref "C28") (pin "1") (pinfunction "1_1") (pintype "passive"))
      (node (ref "C3") (pin "NEG") (pinfunction "NEG_NEG") (pintype "passive"))
      (node (ref "C4") (pin "NEG") (pinfunction "NEG_NEG") (pintype "passive"))
      (node (ref "C40") (pin "1") (pinfunction "1_1") (pintype "passive"))
      (node (ref "C41") (pin "2") (pinfunction "2_2") (pintype "passive"))
      (node (ref "C42") (pin "2") (pinfunction "2_2") (pintype "passive"))
      (node (ref "C43") (pin "2") (pinfunction "2_2") (pintype "passive"))
      (node (ref "C44") (pin "2") (pinfunction "2_2") (pintype "passive"))
      (node (ref "C45") (pin "2") (pinfunction "2_2") (pintype "passive"))
      (node (ref "C46") (pin "2") (pinfunction "2_2") (pintype "passive"))
      (node (ref "C47") (pin "2") (pinfunction "2_2") (pintype "passive"))
      (node (ref "C48") (pin "2") (pinfunction "2_2") (pintype "passive"))
      (node (ref "C5") (pin "1") (pinfunction "1_1") (pintype "passive"))
      (node (ref "C52") (pin "2") (pinfunction "2_2") (pintype "passive"))
      (node (ref "C53") (pin "2") (pinfunction "2_2") (pintype "passive"))
      (node (ref "C54") (pin "2") (pinfunction "2_2") (pintype "passive"))
      (node (ref "C55") (pin "2") (pinfunction "2_2") (pintype "passive"))
      (node (ref "C56") (pin "2") (pinfunction "2_2") (pintype "passive"))
      (node (ref "C57") (pin "2") (pinfunction "2_2") (pintype "passive"))
      (node (ref "C58") (pin "2") (pinfunction "2_2") (pintype "passive"))
      (node (ref "C6") (pin "1") (pinfunction "1_1") (pintype "passive"))
      (node (ref "C63") (pin "1") (pinfunction "1_1") (pintype "passive"))
      (node (ref "C64") (pin "2") (pinfunction "2_2") (pintype "passive"))
      (node (ref "C65") (pin "2") (pinfunction "2_2") (pintype "passive"))
      (node (ref "C66") (pin "2") (pinfunction "2_2") (pintype "passive"))
      (node (ref "C67") (pin "2") (pinfunction "2_2") (pintype "passive"))
      (node (ref "C68") (pin "2") (pinfunction "2_2") (pintype "passive"))
      (node (ref "C69") (pin "2") (pinfunction "2_2") (pintype "passive"))
      (node (ref "C7") (pin "1") (pinfunction "1_1") (pintype "passive"))
      (node (ref "C70") (pin "2") (pinfunction "2_2") (pintype "passive"))
      (node (ref "C71") (pin "2") (pinfunction "2_2") (pintype "passive"))
      (node (ref "C75") (pin "1") (pinfunction "1_1") (pintype "passive"))
      (node (ref "C8") (pin "1") (pinfunction "1_1") (pintype "passive"))
      (node (ref "C9") (pin "1") (pinfunction "1_1") (pintype "passive"))
      (node (ref "J13") (pin "5") (pinfunction "5_5") (pintype "bidirectional"))
      (node (ref "J14") (pin "5") (pinfunction "5_5") (pintype "bidirectional"))
      (node (ref "J15") (pin "5") (pinfunction "5_5") (pintype "bidirectional"))
      (node (ref "J17") (pin "3") (pinfunction "3_3") (pintype "passive"))
      (node (ref "J19") (pin "3") (pinfunction "3_3") (pintype "bidirectional"))
      (node (ref "J2") (pin "3") (pinfunction "3_3") (pintype "bidirectional"))
      (node (ref "J2") (pin "5") (pinfunction "5_5") (pintype "bidirectional"))
      (node (ref "J2") (pin "9") (pinfunction "9_9") (pintype "bidirectional"))
      (node (ref "J5") (pin "3") (pinfunction "3_3") (pintype "passive"))
      (node (ref "J6") (pin "3") (pinfunction "3_3") (pintype "passive"))
      (node (ref "J7") (pin "3") (pinfunction "3_3") (pintype "passive"))
      (node (ref "LED1") (pin "C") (pinfunction "C_C") (pintype "passive"))
      (node (ref "LED2") (pin "C") (pinfunction "C_C") (pintype "passive"))
      (node (ref "LED3") (pin "C") (pinfunction "C_C") (pintype "passive"))
      (node (ref "LED4") (pin "C") (pinfunction "C_C") (pintype "passive"))
      (node (ref "LED5") (pin "C") (pinfunction "C_C") (pintype "passive"))
      (node (ref "R1") (pin "1") (pinfunction "1_1") (pintype "passive"))
      (node (ref "R19") (pin "1") (pinfunction "1_1") (pintype "passive"))
      (node (ref "R2") (pin "1") (pinfunction "1_1") (pintype "passive"))
      (node (ref "R20") (pin "1") (pinfunction "1_1") (pintype "passive"))
      (node (ref "R21") (pin "1") (pinfunction "1_1") (pintype "passive"))
      (node (ref "R39") (pin "1") (pinfunction "1_1") (pintype "passive"))
      (node (ref "R44") (pin "1") (pinfunction "1_1") (pintype "passive"))
      (node (ref "R45") (pin "1") (pinfunction "1_1") (pintype "passive"))
      (node (ref "R46") (pin "1") (pinfunction "1_1") (pintype "passive"))
      (node (ref "R47") (pin "1") (pinfunction "1_1") (pintype "passive"))
      (node (ref "S1") (pin "1") (pinfunction "1_1") (pintype "passive"))
      (node (ref "S2") (pin "1") (pinfunction "1_1") (pintype "passive"))
      (node (ref "S3") (pin "1") (pinfunction "1_1") (pintype "passive"))
      (node (ref "TB1") (pin "3") (pinfunction "3_3") (pintype "passive"))
      (node (ref "TP4") (pin "PAD") (pinfunction "2_PAD") (pintype "passive"))
      (node (ref "U1") (pin "11") (pinfunction "VSSA_11") (pintype "power_in"))
      (node (ref "U1") (pin "15") (pinfunction "VREFN_15") (pintype "power_in"))
      (node (ref "U1") (pin "31") (pinfunction "VSS_31") (pintype "power_in"))
      (node (ref "U1") (pin "41") (pinfunction "VSS_41") (pintype "power_in"))
      (node (ref "U1") (pin "55") (pinfunction "VSS_55") (pintype "power_in"))
      (node (ref "U1") (pin "72") (pinfunction "VSS_72") (pintype "power_in"))
      (node (ref "U1") (pin "83") (pinfunction "VSS_83") (pintype "power_in"))
      (node (ref "U1") (pin "97") (pinfunction "VSS_97") (pintype "power_in"))
      (node (ref "U2") (pin "5") (pinfunction "5_5") (pintype "bidirectional"))
      (node (ref "U3") (pin "3") (pinfunction "GND_3") (pintype "bidirectional"))
      (node (ref "U6") (pin "12") (pinfunction "GNDP_12") (pintype "bidirectional"))
      (node (ref "U6") (pin "18") (pinfunction "DCEN_18") (pintype "bidirectional"))
      (node (ref "U6") (pin "24") (pinfunction "GNDA_24") (pintype "bidirectional"))
      (node (ref "U6") (pin "35") (pinfunction "GNDP_35") (pintype "bidirectional"))
      (node (ref "U6") (pin "36") (pinfunction "TST_MODE_36") (pintype "bidirectional"))
      (node (ref "U6") (pin "PAD") (pinfunction "PAD_PAD") (pintype "bidirectional"))
      (node (ref "U7") (pin "12") (pinfunction "GNDP_12") (pintype "bidirectional"))
      (node (ref "U7") (pin "18") (pinfunction "DCEN_18") (pintype "bidirectional"))
      (node (ref "U7") (pin "24") (pinfunction "GNDA_24") (pintype "bidirectional"))
      (node (ref "U7") (pin "35") (pinfunction "GNDP_35") (pintype "bidirectional"))
      (node (ref "U7") (pin "36") (pinfunction "TST_MODE_36") (pintype "bidirectional"))
      (node (ref "U7") (pin "PAD") (pinfunction "PAD_PAD") (pintype "bidirectional"))
      (node (ref "U8") (pin "12") (pinfunction "GNDP_12") (pintype "bidirectional"))
      (node (ref "U8") (pin "18") (pinfunction "DCEN_18") (pintype "bidirectional"))
      (node (ref "U8") (pin "24") (pinfunction "GNDA_24") (pintype "bidirectional"))
      (node (ref "U8") (pin "35") (pinfunction "GNDP_35") (pintype "bidirectional"))
      (node (ref "U8") (pin "36") (pinfunction "TST_MODE_36") (pintype "bidirectional"))
      (node (ref "U8") (pin "PAD") (pinfunction "PAD_PAD") (pintype "bidirectional"))
      (node (ref "VR1") (pin "1") (pinfunction "GND_1") (pintype "bidirectional"))
    )
    (net (code "31") (name "ISP_COM") (class "Default")
      (node (ref "R4") (pin "1") (pinfunction "1_1") (pintype "passive"))
      (node (ref "S2") (pin "2") (pinfunction "2_2") (pintype "passive"))
      (node (ref "U1") (pin "53") (pinfunction "P2-10_53") (pintype "bidirectional"))
    )
    (net (code "32") (name "MISO") (class "Default")
      (node (ref "U1") (pin "77") (pinfunction "P0-8_77") (pintype "bidirectional"))
      (node (ref "U6") (pin "5") (pinfunction "SDO_5") (pintype "bidirectional"))
      (node (ref "U7") (pin "5") (pinfunction "SDO_5") (pintype "bidirectional"))
      (node (ref "U8") (pin "5") (pinfunction "SDO_5") (pintype "bidirectional"))
    )
    (net (code "33") (name "MOSI") (class "Default")
      (node (ref "U1") (pin "76") (pinfunction "P0-9_76") (pintype "bidirectional"))
      (node (ref "U6") (pin "4") (pinfunction "SDI_4") (pintype "bidirectional"))
      (node (ref "U7") (pin "4") (pinfunction "SDI_4") (pintype "bidirectional"))
      (node (ref "U8") (pin "4") (pinfunction "SDI_4") (pintype "bidirectional"))
    )
    (net (code "34") (name "Net-(D3-A)") (class "Default")
      (node (ref "C48") (pin "1") (pinfunction "1_1") (pintype "passive"))
      (node (ref "D3") (pin "POS") (pinfunction "A_POS") (pintype "passive"))
      (node (ref "D4") (pin "POS") (pinfunction "A_POS") (pintype "passive"))
      (node (ref "R44") (pin "2") (pinfunction "2_2") (pintype "passive"))
      (node (ref "U6") (pin "33") (pinfunction "BRA_33") (pintype "bidirectional"))
    )
    (net (code "35") (name "Net-(D5-A)") (class "Default")
      (node (ref "C47") (pin "1") (pinfunction "1_1") (pintype "passive"))
      (node (ref "D5") (pin "POS") (pinfunction "A_POS") (pintype "passive"))
      (node (ref "D6") (pin "POS") (pinfunction "A_POS") (pintype "passive"))
      (node (ref "R45") (pin "2") (pinfunction "2_2") (pintype "passive"))
      (node (ref "U6") (pin "14") (pinfunction "BRB_14") (pintype "bidirectional"))
    )
    (net (code "36") (name "Net-(D7-A)") (class "Default")
      (node (ref "C58") (pin "1") (pinfunction "1_1") (pintype "passive"))
      (node (ref "D7") (pin "POS") (pinfunction "A_POS") (pintype "passive"))
      (node (ref "D8") (pin "POS") (pinfunction "A_POS") (pintype "passive"))
      (node (ref "R1") (pin "2") (pinfunction "2_2") (pintype "passive"))
      (node (ref "U8") (pin "33") (pinfunction "BRA_33") (pintype "bidirectional"))
    )
    (net (code "37") (name "Net-(D10-A)") (class "Default")
      (node (ref "C57") (pin "1") (pinfunction "1_1") (pintype "passive"))
      (node (ref "D10") (pin "POS") (pinfunction "A_POS") (pintype "passive"))
      (node (ref "D9") (pin "POS") (pinfunction "A_POS") (pintype "passive"))
      (node (ref "R2") (pin "2") (pinfunction "2_2") (pintype "passive"))
      (node (ref "U8") (pin "14") (pinfunction "BRB_14") (pintype "bidirectional"))
    )
    (net (code "38") (name "Net-(D11-A)") (class "Default")
      (node (ref "C71") (pin "1") (pinfunction "1_1") (pintype "passive"))
      (node (ref "D11") (pin "POS") (pinfunction "A_POS") (pintype "passive"))
      (node (ref "D12") (pin "POS") (pinfunction "A_POS") (pintype "passive"))
      (node (ref "R46") (pin "2") (pinfunction "2_2") (pintype "passive"))
      (node (ref "U7") (pin "33") (pinfunction "BRA_33") (pintype "bidirectional"))
    )
    (net (code "39") (name "Net-(D13-A)") (class "Default")
      (node (ref "C70") (pin "1") (pinfunction "1_1") (pintype "passive"))
      (node (ref "D13") (pin "POS") (pinfunction "A_POS") (pintype "passive"))
      (node (ref "D14") (pin "POS") (pinfunction "A_POS") (pintype "passive"))
      (node (ref "R47") (pin "2") (pinfunction "2_2") (pintype "passive"))
      (node (ref "U7") (pin "14") (pinfunction "BRB_14") (pintype "bidirectional"))
    )
    (net (code "40") (name "Net-(LED1-PadA)") (class "Default")
      (node (ref "LED1") (pin "A") (pinfunction "A_A") (pintype "passive"))
      (node (ref "R6") (pin "1") (pinfunction "1_1") (pintype "passive"))
    )
    (net (code "41") (name "Net-(LED2-PadA)") (class "Default")
      (node (ref "LED2") (pin "A") (pinfunction "A_A") (pintype "passive"))
      (node (ref "R7") (pin "1") (pinfunction "1_1") (pintype "passive"))
    )
    (net (code "42") (name "Net-(LED3-PadA)") (class "Default")
      (node (ref "LED3") (pin "A") (pinfunction "A_A") (pintype "passive"))
      (node (ref "R8") (pin "1") (pinfunction "1_1") (pintype "passive"))
    )
    (net (code "43") (name "Net-(LED4-PadA)") (class "Default")
      (node (ref "LED4") (pin "A") (pinfunction "A_A") (pintype "passive"))
      (node (ref "R9") (pin "1") (pinfunction "1_1") (pintype "passive"))
    )
    (net (code "44") (name "Net-(LED5-PadA)") (class "Default")
      (node (ref "LED5") (pin "A") (pinfunction "A_A") (pintype "passive"))
      (node (ref "R41") (pin "1") (pinfunction "1_1") (pintype "passive"))
    )
    (net (code "45") (name "Net-(U1-VDDA)") (class "Default")
      (node (ref "C27") (pin "2") (pinfunction "2_2") (pintype "passive"))
      (node (ref "C28") (pin "2") (pinfunction "2_2") (pintype "passive"))
      (node (ref "FB2") (pin "1") (pinfunction "1_1") (pintype "passive"))
      (node (ref "U1") (pin "10") (pinfunction "VDDA_10") (pintype "power_in"))
      (node (ref "U1") (pin "12") (pinfunction "VREFP_12") (pintype "power_in"))
    )
    (net (code "46") (name "Net-(U6-5VOUT)") (class "Default")
      (node (ref "C12") (pin "2") (pinfunction "2_2") (pintype "passive"))
      (node (ref "R10") (pin "1") (pinfunction "1_1") (pintype "passive"))
      (node (ref "U6") (pin "25") (pinfunction "5VOUT_25") (pintype "bidirectional"))
    )
    (net (code "47") (name "Net-(U6-CPI)") (class "Default")
      (node (ref "C49") (pin "2") (pinfunction "2_2") (pintype "passive"))
      (node (ref "U6") (pin "28") (pinfunction "CPI_28") (pintype "bidirectional"))
    )
    (net (code "48") (name "Net-(U6-CPO)") (class "Default")
      (node (ref "C49") (pin "1") (pinfunction "1_1") (pintype "passive"))
      (node (ref "U6") (pin "27") (pinfunction "CPO_27") (pintype "bidirectional"))
    )
    (net (code "49") (name "Net-(U6-VCC)") (class "Default")
      (node (ref "C11") (pin "2") (pinfunction "2_2") (pintype "passive"))
      (node (ref "R10") (pin "2") (pinfunction "2_2") (pintype "passive"))
      (node (ref "U6") (pin "26") (pinfunction "VCC_26") (pintype "bidirectional"))
      (node (ref "U6") (pin "8") (pinfunction "VCC_IO_8") (pintype "bidirectional"))
    )
    (net (code "50") (name "Net-(U6-VCP)") (class "Default")
      (node (ref "C39") (pin "1") (pinfunction "1_1") (pintype "passive"))
      (node (ref "U6") (pin "29") (pinfunction "VCP_29") (pintype "bidirectional"))
    )
    (net (code "51") (name "Net-(U7-5VOUT)") (class "Default")
      (node (ref "C14") (pin "2") (pinfunction "2_2") (pintype "passive"))
      (node (ref "R12") (pin "1") (pinfunction "1_1") (pintype "passive"))
      (node (ref "U7") (pin "25") (pinfunction "5VOUT_25") (pintype "bidirectional"))
    )
    (net (code "52") (name "Net-(U7-CPI)") (class "Default")
      (node (ref "C72") (pin "2") (pinfunction "2_2") (pintype "passive"))
      (node (ref "U7") (pin "28") (pinfunction "CPI_28") (pintype "bidirectional"))
    )
    (net (code "53") (name "Net-(U7-CPO)") (class "Default")
      (node (ref "C72") (pin "1") (pinfunction "1_1") (pintype "passive"))
      (node (ref "U7") (pin "27") (pinfunction "CPO_27") (pintype "bidirectional"))
    )
    (net (code "54") (name "Net-(U7-VCC)") (class "Default")
      (node (ref "C13") (pin "2") (pinfunction "2_2") (pintype "passive"))
      (node (ref "R12") (pin "2") (pinfunction "2_2") (pintype "passive"))
      (node (ref "U7") (pin "26") (pinfunction "VCC_26") (pintype "bidirectional"))
      (node (ref "U7") (pin "8") (pinfunction "VCC_IO_8") (pintype "bidirectional"))
    )
    (net (code "55") (name "Net-(U7-VCP)") (class "Default")
      (node (ref "C62") (pin "1") (pinfunction "1_1") (pintype "passive"))
      (node (ref "U7") (pin "29") (pinfunction "VCP_29") (pintype "bidirectional"))
    )
    (net (code "56") (name "Net-(U8-5VOUT)") (class "Default")
      (node (ref "C19") (pin "2") (pinfunction "2_2") (pintype "passive"))
      (node (ref "R11") (pin "1") (pinfunction "1_1") (pintype "passive"))
      (node (ref "U8") (pin "25") (pinfunction "5VOUT_25") (pintype "bidirectional"))
    )
    (net (code "57") (name "Net-(U8-CPI)") (class "Default")
      (node (ref "C59") (pin "2") (pinfunction "2_2") (pintype "passive"))
      (node (ref "U8") (pin "28") (pinfunction "CPI_28") (pintype "bidirectional"))
    )
    (net (code "58") (name "Net-(U8-CPO)") (class "Default")
      (node (ref "C59") (pin "1") (pinfunction "1_1") (pintype "passive"))
      (node (ref "U8") (pin "27") (pinfunction "CPO_27") (pintype "bidirectional"))
    )
    (net (code "59") (name "Net-(U8-VCC)") (class "Default")
      (node (ref "C18") (pin "2") (pinfunction "2_2") (pintype "passive"))
      (node (ref "R11") (pin "2") (pinfunction "2_2") (pintype "passive"))
      (node (ref "U8") (pin "26") (pinfunction "VCC_26") (pintype "bidirectional"))
      (node (ref "U8") (pin "8") (pinfunction "VCC_IO_8") (pintype "bidirectional"))
    )
    (net (code "60") (name "Net-(U8-VCP)") (class "Default")
      (node (ref "C15") (pin "1") (pinfunction "1_1") (pintype "passive"))
      (node (ref "U8") (pin "29") (pinfunction "VCP_29") (pintype "bidirectional"))
    )
    (net (code "61") (name "RESET") (class "Default")
      (node (ref "C29") (pin "2") (pinfunction "2_2") (pintype "passive"))
      (node (ref "R18") (pin "1") (pinfunction "1_1") (pintype "passive"))
      (node (ref "S1") (pin "2") (pinfunction "2_2") (pintype "passive"))
      (node (ref "U1") (pin "17") (pinfunction "RESET_17") (pintype "input"))
    )
    (net (code "62") (name "RESET_N") (class "Default")
      (node (ref "J2") (pin "10") (pinfunction "10_10") (pintype "bidirectional"))
      (node (ref "U1") (pin "4") (pinfunction "TRST_4") (pintype "input"))
    )
    (net (code "63") (name "RO1") (class "Default")
      (node (ref "U1") (pin "63") (pinfunction "P0-16_63") (pintype "bidirectional"))
      (node (ref "U2") (pin "1") (pinfunction "1_1") (pintype "bidirectional"))
    )
    (net (code "64") (name "RTCK") (class "Default")
      (node (ref "J2") (pin "7") (pinfunction "7_7") (pintype "bidirectional"))
      (node (ref "U1") (pin "100") (pinfunction "RTCK_100") (pintype "output"))
    )
    (net (code "65") (name "SCK") (class "Default")
      (node (ref "U1") (pin "78") (pinfunction "P0-7_78") (pintype "bidirectional"))
      (node (ref "U6") (pin "3") (pinfunction "SCK_3") (pintype "bidirectional"))
      (node (ref "U7") (pin "3") (pinfunction "SCK_3") (pintype "bidirectional"))
      (node (ref "U8") (pin "3") (pinfunction "SCK_3") (pintype "bidirectional"))
    )
    (net (code "66") (name "SPI_~{CS1}") (class "Default")
      (node (ref "U1") (pin "9") (pinfunction "P0-23_9") (pintype "bidirectional"))
      (node (ref "U6") (pin "2") (pinfunction "~{CS}_2") (pintype "bidirectional"))
    )
    (net (code "67") (name "SPI_~{CS2}") (class "Default")
      (node (ref "U1") (pin "8") (pinfunction "P0-24_8") (pintype "bidirectional"))
      (node (ref "U7") (pin "2") (pinfunction "~{CS}_2") (pintype "bidirectional"))
    )
    (net (code "68") (name "SPI_~{CS3}") (class "Default")
      (node (ref "U1") (pin "7") (pinfunction "P0-25_7") (pintype "bidirectional"))
      (node (ref "U8") (pin "2") (pinfunction "~{CS}_2") (pintype "bidirectional"))
    )
    (net (code "69") (name "STAT_LED4") (class "Default")
      (node (ref "R6") (pin "2") (pinfunction "2_2") (pintype "passive"))
      (node (ref "U1") (pin "37") (pinfunction "P1-23_37") (pintype "bidirectional"))
    )
    (net (code "70") (name "STAT_LED5") (class "Default")
      (node (ref "R7") (pin "2") (pinfunction "2_2") (pintype "passive"))
      (node (ref "U1") (pin "36") (pinfunction "P1-22_36") (pintype "bidirectional"))
    )
    (net (code "71") (name "STAT_LED6") (class "Default")
      (node (ref "R8") (pin "2") (pinfunction "2_2") (pintype "passive"))
      (node (ref "U1") (pin "35") (pinfunction "P1-21_35") (pintype "bidirectional"))
    )
    (net (code "72") (name "STAT_LED7") (class "Default")
      (node (ref "R9") (pin "2") (pinfunction "2_2") (pintype "passive"))
      (node (ref "U1") (pin "34") (pinfunction "P1-20_34") (pintype "bidirectional"))
    )
    (net (code "73") (name "SWDCLK") (class "Default")
      (node (ref "J2") (pin "4") (pinfunction "4_4") (pintype "bidirectional"))
      (node (ref "U1") (pin "5") (pinfunction "TCK/SWDCLK_5") (pintype "input"))
    )
    (net (code "74") (name "SWDIO") (class "Default")
      (node (ref "J2") (pin "2") (pinfunction "2_2") (pintype "bidirectional"))
      (node (ref "U1") (pin "3") (pinfunction "TMS_3") (pintype "input"))
    )
    (net (code "75") (name "SWO") (class "Default")
      (node (ref "J2") (pin "6") (pinfunction "6_6") (pintype "bidirectional"))
      (node (ref "U1") (pin "1") (pinfunction "TDO_1") (pintype "output"))
    )
    (net (code "76") (name "TDI") (class "Default")
      (node (ref "J2") (pin "8") (pinfunction "8_8") (pintype "bidirectional"))
      (node (ref "U1") (pin "2") (pinfunction "TDI_2") (pintype "input"))
    )
    (net (code "77") (name "USBMCU+") (class "Default")
      (node (ref "J17") (pin "7") (pinfunction "7_7") (pintype "passive"))
      (node (ref "U1") (pin "29") (pinfunction "P0-29_29") (pintype "bidirectional"))
    )
    (net (code "78") (name "USBMCU-") (class "Default")
      (node (ref "J17") (pin "8") (pinfunction "8_8") (pintype "passive"))
      (node (ref "U1") (pin "30") (pinfunction "P0-30_30") (pintype "bidirectional"))
    )
    (net (code "79") (name "XTAL1") (class "Default")
      (node (ref "C1") (pin "2") (pinfunction "2_2") (pintype "passive"))
      (node (ref "Q1") (pin "1") (pinfunction "1_1") (pintype "passive"))
      (node (ref "R3") (pin "1") (pinfunction "1_1") (pintype "passive"))
      (node (ref "U1") (pin "22") (pinfunction "XTAL1_22") (pintype "input"))
    )
    (net (code "80") (name "XTAL2") (class "Default")
      (node (ref "C75") (pin "2") (pinfunction "2_2") (pintype "passive"))
      (node (ref "Q1") (pin "2") (pinfunction "2_2") (pintype "passive"))
      (node (ref "R3") (pin "2") (pinfunction "2_2") (pintype "passive"))
      (node (ref "U1") (pin "23") (pinfunction "XTAL2_23") (pintype "output"))
    )
    (net (code "81") (name "X_DIR") (class "Default")
      (node (ref "U6") (pin "7") (pinfunction "DIR_7") (pintype "bidirectional"))
    )
    (net (code "82") (name "X_INDEX") (class "Default")
      (node (ref "J13") (pin "4") (pinfunction "4_4") (pintype "bidirectional"))
    )
    (net (code "83") (name "X_MIN") (class "Default")
      (node (ref "R19") (pin "2") (pinfunction "2_2") (pintype "passive"))
      (node (ref "R26") (pin "1") (pinfunction "1_1") (pintype "passive"))
      (node (ref "U1") (pin "40") (pinfunction "P1-26_40") (pintype "bidirectional"))
    )
    (net (code "84") (name "X_STEP") (class "Default")
      (node (ref "U6") (pin "6") (pinfunction "STEP_6") (pintype "bidirectional"))
    )
    (net (code "85") (name "X_STOP") (class "Default")
      (node (ref "J5") (pin "1") (pinfunction "1_1") (pintype "passive"))
      (node (ref "R26") (pin "2") (pinfunction "2_2") (pintype "passive"))
    )
    (net (code "86") (name "Y_DIR") (class "Default")
      (node (ref "U7") (pin "7") (pinfunction "DIR_7") (pintype "bidirectional"))
    )
    (net (code "87") (name "Y_INDEX") (class "Default")
      (node (ref "J14") (pin "4") (pinfunction "4_4") (pintype "bidirectional"))
    )
    (net (code "88") (name "Y_MIN") (class "Default")
      (node (ref "R20") (pin "2") (pinfunction "2_2") (pintype "passive"))
      (node (ref "R25") (pin "1") (pinfunction "1_1") (pintype "passive"))
      (node (ref "U1") (pin "43") (pinfunction "P1-27_43") (pintype "bidirectional"))
    )
    (net (code "89") (name "Y_STEP") (class "Default")
      (node (ref "U7") (pin "6") (pinfunction "STEP_6") (pintype "bidirectional"))
    )
    (net (code "90") (name "Y_STOP") (class "Default")
      (node (ref "J6") (pin "1") (pinfunction "1_1") (pintype "passive"))
      (node (ref "R25") (pin "2") (pinfunction "2_2") (pintype "passive"))
    )
    (net (code "91") (name "Z_DIR") (class "Default")
      (node (ref "U8") (pin "7") (pinfunction "DIR_7") (pintype "bidirectional"))
    )
    (net (code "92") (name "Z_INDEX") (class "Default")
      (node (ref "J15") (pin "4") (pinfunction "4_4") (pintype "bidirectional"))
    )
    (net (code "93") (name "Z_MIN") (class "Default")
      (node (ref "R21") (pin "2") (pinfunction "2_2") (pintype "passive"))
      (node (ref "R24") (pin "1") (pinfunction "1_1") (pintype "passive"))
      (node (ref "U1") (pin "44") (pinfunction "P1-28_44") (pintype "bidirectional"))
    )
    (net (code "94") (name "Z_STEP") (class "Default")
      (node (ref "U8") (pin "6") (pinfunction "STEP_6") (pintype "bidirectional"))
    )
    (net (code "95") (name "Z_STOP") (class "Default")
      (node (ref "J7") (pin "1") (pinfunction "1_1") (pintype "passive"))
      (node (ref "R24") (pin "2") (pinfunction "2_2") (pintype "passive"))
    )
    (net (code "96") (name "unconnected-(J1-Pad1)") (class "Default")
      (node (ref "J1") (pin "1") (pinfunction "1_1") (pintype "bidirectional"))
    )
    (net (code "97") (name "unconnected-(J1-Pad2)") (class "Default")
      (node (ref "J1") (pin "2") (pinfunction "2_2") (pintype "bidirectional"))
    )
    (net (code "98") (name "unconnected-(J1-Pad4)") (class "Default")
      (node (ref "J1") (pin "4") (pinfunction "4_4") (pintype "bidirectional"))
    )
    (net (code "99") (name "unconnected-(J1-Pad5)") (class "Default")
      (node (ref "J1") (pin "5") (pinfunction "5_5") (pintype "bidirectional"))
    )
    (net (code "100") (name "unconnected-(U1-N{slash}C-Pad13)") (class "Default")
      (node (ref "U1") (pin "13") (pinfunction "N/C_13") (pintype "no_connect"))
    )
    (net (code "101") (name "unconnected-(U1-P0-0-Pad46)") (class "Default")
      (node (ref "U1") (pin "46") (pinfunction "P0-0_46") (pintype "bidirectional"))
    )
    (net (code "102") (name "unconnected-(U1-P0-1-Pad47)") (class "Default")
      (node (ref "U1") (pin "47") (pinfunction "P0-1_47") (pintype "bidirectional"))
    )
    (net (code "103") (name "unconnected-(U1-P0-2-Pad98)") (class "Default")
      (node (ref "U1") (pin "98") (pinfunction "P0-2_98") (pintype "bidirectional"))
    )
    (net (code "104") (name "unconnected-(U1-P0-3-Pad99)") (class "Default")
      (node (ref "U1") (pin "99") (pinfunction "P0-3_99") (pintype "bidirectional"))
    )
    (net (code "105") (name "unconnected-(U1-P0-4-Pad81)") (class "Default")
      (node (ref "U1") (pin "81") (pinfunction "P0-4_81") (pintype "bidirectional"))
    )
    (net (code "106") (name "unconnected-(U1-P0-5-Pad80)") (class "Default")
      (node (ref "U1") (pin "80") (pinfunction "P0-5_80") (pintype "bidirectional"))
    )
    (net (code "107") (name "unconnected-(U1-P0-6-Pad79)") (class "Default")
      (node (ref "U1") (pin "79") (pinfunction "P0-6_79") (pintype "bidirectional"))
    )
    (net (code "108") (name "unconnected-(U1-P0-10-Pad48)") (class "Default")
      (node (ref "U1") (pin "48") (pinfunction "P0-10_48") (pintype "bidirectional"))
    )
    (net (code "109") (name "unconnected-(U1-P0-17-Pad61)") (class "Default")
      (node (ref "U1") (pin "61") (pinfunction "P0-17_61") (pintype "bidirectional"))
    )
    (net (code "110") (name "unconnected-(U1-P0-18-Pad60)") (class "Default")
      (node (ref "U1") (pin "60") (pinfunction "P0-18_60") (pintype "bidirectional"))
    )
    (net (code "111") (name "unconnected-(U1-P0-19-Pad59)") (class "Default")
      (node (ref "U1") (pin "59") (pinfunction "P0-19_59") (pintype "bidirectional"))
    )
    (net (code "112") (name "unconnected-(U1-P0-21-Pad57)") (class "Default")
      (node (ref "U1") (pin "57") (pinfunction "P0-21_57") (pintype "bidirectional"))
    )
    (net (code "113") (name "unconnected-(U1-P0-22-Pad56)") (class "Default")
      (node (ref "U1") (pin "56") (pinfunction "P0-22_56") (pintype "bidirectional"))
    )
    (net (code "114") (name "unconnected-(U1-P0-26-Pad6)") (class "Default")
      (node (ref "U1") (pin "6") (pinfunction "P0-26_6") (pintype "bidirectional"))
    )
    (net (code "115") (name "unconnected-(U1-P0-27-Pad25)") (class "Default")
      (node (ref "U1") (pin "25") (pinfunction "P0-27_25") (pintype "bidirectional"))
    )
    (net (code "116") (name "unconnected-(U1-P0-28-Pad24)") (class "Default")
      (node (ref "U1") (pin "24") (pinfunction "P0-28_24") (pintype "bidirectional"))
    )
    (net (code "117") (name "unconnected-(U1-P1-0-Pad95)") (class "Default")
      (node (ref "U1") (pin "95") (pinfunction "P1-0_95") (pintype "bidirectional"))
    )
    (net (code "118") (name "unconnected-(U1-P1-1-Pad94)") (class "Default")
      (node (ref "U1") (pin "94") (pinfunction "P1-1_94") (pintype "bidirectional"))
    )
    (net (code "119") (name "unconnected-(U1-P1-4-Pad93)") (class "Default")
      (node (ref "U1") (pin "93") (pinfunction "P1-4_93") (pintype "bidirectional"))
    )
    (net (code "120") (name "unconnected-(U1-P1-8-Pad92)") (class "Default")
      (node (ref "U1") (pin "92") (pinfunction "P1-8_92") (pintype "bidirectional"))
    )
    (net (code "121") (name "unconnected-(U1-P1-9-Pad91)") (class "Default")
      (node (ref "U1") (pin "91") (pinfunction "P1-9_91") (pintype "bidirectional"))
    )
    (net (code "122") (name "unconnected-(U1-P1-10-Pad90)") (class "Default")
      (node (ref "U1") (pin "90") (pinfunction "P1-10_90") (pintype "bidirectional"))
    )
    (net (code "123") (name "unconnected-(U1-P1-14-Pad89)") (class "Default")
      (node (ref "U1") (pin "89") (pinfunction "P1-14_89") (pintype "bidirectional"))
    )
    (net (code "124") (name "unconnected-(U1-P1-15-Pad88)") (class "Default")
      (node (ref "U1") (pin "88") (pinfunction "P1-15_88") (pintype "bidirectional"))
    )
    (net (code "125") (name "unconnected-(U1-P1-16-Pad87)") (class "Default")
      (node (ref "U1") (pin "87") (pinfunction "P1-16_87") (pintype "bidirectional"))
    )
    (net (code "126") (name "unconnected-(U1-P1-17-Pad86)") (class "Default")
      (node (ref "U1") (pin "86") (pinfunction "P1-17_86") (pintype "bidirectional"))
    )
    (net (code "127") (name "unconnected-(U1-P1-18-Pad32)") (class "Default")
      (node (ref "U1") (pin "32") (pinfunction "P1-18_32") (pintype "bidirectional"))
    )
    (net (code "128") (name "unconnected-(U1-P1-29-Pad45)") (class "Default")
      (node (ref "U1") (pin "45") (pinfunction "P1-29_45") (pintype "bidirectional"))
    )
    (net (code "129") (name "unconnected-(U1-P1-30-Pad21)") (class "Default")
      (node (ref "U1") (pin "21") (pinfunction "P1-30_21") (pintype "bidirectional"))
    )
    (net (code "130") (name "unconnected-(U1-P1-31-Pad20)") (class "Default")
      (node (ref "U1") (pin "20") (pinfunction "P1-31_20") (pintype "bidirectional"))
    )
    (net (code "131") (name "unconnected-(U1-P2-0-Pad75)") (class "Default")
      (node (ref "U1") (pin "75") (pinfunction "P2-0_75") (pintype "bidirectional"))
    )
    (net (code "132") (name "unconnected-(U1-P2-1-Pad74)") (class "Default")
      (node (ref "U1") (pin "74") (pinfunction "P2-1_74") (pintype "bidirectional"))
    )
    (net (code "133") (name "unconnected-(U1-P2-2-Pad73)") (class "Default")
      (node (ref "U1") (pin "73") (pinfunction "P2-2_73") (pintype "bidirectional"))
    )
    (net (code "134") (name "unconnected-(U1-P2-3-Pad70)") (class "Default")
      (node (ref "U1") (pin "70") (pinfunction "P2-3_70") (pintype "bidirectional"))
    )
    (net (code "135") (name "unconnected-(U1-P2-4-Pad69)") (class "Default")
      (node (ref "U1") (pin "69") (pinfunction "P2-4_69") (pintype "bidirectional"))
    )
    (net (code "136") (name "unconnected-(U1-P2-5-Pad68)") (class "Default")
      (node (ref "U1") (pin "68") (pinfunction "P2-5_68") (pintype "bidirectional"))
    )
    (net (code "137") (name "unconnected-(U1-P2-6-Pad67)") (class "Default")
      (node (ref "U1") (pin "67") (pinfunction "P2-6_67") (pintype "bidirectional"))
    )
    (net (code "138") (name "unconnected-(U1-P2-7-Pad66)") (class "Default")
      (node (ref "U1") (pin "66") (pinfunction "P2-7_66") (pintype "bidirectional"))
    )
    (net (code "139") (name "unconnected-(U1-P2-8-Pad65)") (class "Default")
      (node (ref "U1") (pin "65") (pinfunction "P2-8_65") (pintype "bidirectional"))
    )
    (net (code "140") (name "unconnected-(U1-P2-9-Pad64)") (class "Default")
      (node (ref "U1") (pin "64") (pinfunction "P2-9_64") (pintype "bidirectional"))
    )
    (net (code "141") (name "unconnected-(U1-P2-11-Pad52)") (class "Default")
      (node (ref "U1") (pin "52") (pinfunction "P2-11_52") (pintype "bidirectional"))
    )
    (net (code "142") (name "unconnected-(U1-P2-12-Pad51)") (class "Default")
      (node (ref "U1") (pin "51") (pinfunction "P2-12_51") (pintype "bidirectional"))
    )
    (net (code "143") (name "unconnected-(U1-P2-13-Pad50)") (class "Default")
      (node (ref "U1") (pin "50") (pinfunction "P2-13_50") (pintype "bidirectional"))
    )
    (net (code "144") (name "unconnected-(U1-P3-25-Pad27)") (class "Default")
      (node (ref "U1") (pin "27") (pinfunction "P3-25_27") (pintype "bidirectional"))
    )
    (net (code "145") (name "unconnected-(U1-P3-26-Pad26)") (class "Default")
      (node (ref "U1") (pin "26") (pinfunction "P3-26_26") (pintype "bidirectional"))
    )
    (net (code "146") (name "unconnected-(U1-P4-28-Pad82)") (class "Default")
      (node (ref "U1") (pin "82") (pinfunction "P4-28_82") (pintype "bidirectional"))
    )
    (net (code "147") (name "unconnected-(U1-P4-29-Pad85)") (class "Default")
      (node (ref "U1") (pin "85") (pinfunction "P4-29_85") (pintype "bidirectional"))
    )
    (net (code "148") (name "unconnected-(U1-RSTOUT-Pad14)") (class "Default")
      (node (ref "U1") (pin "14") (pinfunction "RSTOUT_14") (pintype "output"))
    )
    (net (code "149") (name "unconnected-(U1-RTCX1-Pad16)") (class "Default")
      (node (ref "U1") (pin "16") (pinfunction "RTCX1_16") (pintype "input"))
    )
    (net (code "150") (name "unconnected-(U1-RTCX2-Pad18)") (class "Default")
      (node (ref "U1") (pin "18") (pinfunction "RTCX2_18") (pintype "output"))
    )
    (net (code "151") (name "unconnected-(U6-AIN_IREF-Pad23)") (class "Default")
      (node (ref "U6") (pin "23") (pinfunction "AIN_IREF_23") (pintype "bidirectional"))
    )
    (net (code "152") (name "unconnected-(U6-DCIN-Pad19)") (class "Default")
      (node (ref "U6") (pin "19") (pinfunction "DCIN_19") (pintype "bidirectional"))
    )
    (net (code "153") (name "unconnected-(U6-DCO-Pad17)") (class "Default")
      (node (ref "U6") (pin "17") (pinfunction "DCO_17") (pintype "bidirectional"))
    )
    (net (code "154") (name "unconnected-(U6-DIAG0-Pad20)") (class "Default")
      (node (ref "U6") (pin "20") (pinfunction "DIAG0_20") (pintype "bidirectional"))
    )
    (net (code "155") (name "unconnected-(U6-DIAG1-Pad21)") (class "Default")
      (node (ref "U6") (pin "21") (pinfunction "DIAG1_21") (pintype "bidirectional"))
    )
    (net (code "156") (name "unconnected-(U6-DNC-Pad9)") (class "Default")
      (node (ref "U6") (pin "9") (pinfunction "DNC_9") (pintype "bidirectional"))
    )
    (net (code "157") (name "unconnected-(U6-N.C.-Pad11)") (class "Default")
      (node (ref "U6") (pin "11") (pinfunction "N.C._11") (pintype "bidirectional"))
    )
    (net (code "158") (name "unconnected-(U6-SPI_MODE-Pad10)") (class "Default")
      (node (ref "U6") (pin "10") (pinfunction "SPI_MODE_10") (pintype "bidirectional"))
    )
    (net (code "159") (name "unconnected-(U7-AIN_IREF-Pad23)") (class "Default")
      (node (ref "U7") (pin "23") (pinfunction "AIN_IREF_23") (pintype "bidirectional"))
    )
    (net (code "160") (name "unconnected-(U7-DCIN-Pad19)") (class "Default")
      (node (ref "U7") (pin "19") (pinfunction "DCIN_19") (pintype "bidirectional"))
    )
    (net (code "161") (name "unconnected-(U7-DCO-Pad17)") (class "Default")
      (node (ref "U7") (pin "17") (pinfunction "DCO_17") (pintype "bidirectional"))
    )
    (net (code "162") (name "unconnected-(U7-DIAG0-Pad20)") (class "Default")
      (node (ref "U7") (pin "20") (pinfunction "DIAG0_20") (pintype "bidirectional"))
    )
    (net (code "163") (name "unconnected-(U7-DIAG1-Pad21)") (class "Default")
      (node (ref "U7") (pin "21") (pinfunction "DIAG1_21") (pintype "bidirectional"))
    )
    (net (code "164") (name "unconnected-(U7-DNC-Pad9)") (class "Default")
      (node (ref "U7") (pin "9") (pinfunction "DNC_9") (pintype "bidirectional"))
    )
    (net (code "165") (name "unconnected-(U7-N.C.-Pad11)") (class "Default")
      (node (ref "U7") (pin "11") (pinfunction "N.C._11") (pintype "bidirectional"))
    )
    (net (code "166") (name "unconnected-(U7-SPI_MODE-Pad10)") (class "Default")
      (node (ref "U7") (pin "10") (pinfunction "SPI_MODE_10") (pintype "bidirectional"))
    )
    (net (code "167") (name "unconnected-(U8-AIN_IREF-Pad23)") (class "Default")
      (node (ref "U8") (pin "23") (pinfunction "AIN_IREF_23") (pintype "bidirectional"))
    )
    (net (code "168") (name "unconnected-(U8-DCIN-Pad19)") (class "Default")
      (node (ref "U8") (pin "19") (pinfunction "DCIN_19") (pintype "bidirectional"))
    )
    (net (code "169") (name "unconnected-(U8-DCO-Pad17)") (class "Default")
      (node (ref "U8") (pin "17") (pinfunction "DCO_17") (pintype "bidirectional"))
    )
    (net (code "170") (name "unconnected-(U8-DIAG0-Pad20)") (class "Default")
      (node (ref "U8") (pin "20") (pinfunction "DIAG0_20") (pintype "bidirectional"))
    )
    (net (code "171") (name "unconnected-(U8-DIAG1-Pad21)") (class "Default")
      (node (ref "U8") (pin "21") (pinfunction "DIAG1_21") (pintype "bidirectional"))
    )
    (net (code "172") (name "unconnected-(U8-DNC-Pad9)") (class "Default")
      (node (ref "U8") (pin "9") (pinfunction "DNC_9") (pintype "bidirectional"))
    )
    (net (code "173") (name "unconnected-(U8-N.C.-Pad11)") (class "Default")
      (node (ref "U8") (pin "11") (pinfunction "N.C._11") (pintype "bidirectional"))
    )
    (net (code "174") (name "unconnected-(U8-SPI_MODE-Pad10)") (class "Default")
      (node (ref "U8") (pin "10") (pinfunction "SPI_MODE_10") (pintype "bidirectional"))
    )
    (net (code "175") (name "unconnected-(VR1-OUT-Pad2)") (class "Default")
      (node (ref "VR1") (pin "2") (pinfunction "OUT_2") (pintype "bidirectional"))
    )
    (net (code "176") (name "~{ENABLE_LPC}") (class "Default")
      (node (ref "U1") (pin "38") (pinfunction "P1-24_38") (pintype "bidirectional"))
      (node (ref "U3") (pin "2") (pinfunction "B_2") (pintype "bidirectional"))
    )
    (net (code "177") (name "~{ENABLE_MOD}") (class "Default")
      (node (ref "J17") (pin "2") (pinfunction "2_2") (pintype "passive"))
      (node (ref "J19") (pin "2") (pinfunction "2_2") (pintype "bidirectional"))
      (node (ref "U3") (pin "1") (pinfunction "A_1") (pintype "bidirectional"))
    )
    (net (code "178") (name "~{ENABLE}") (class "Default")
      (node (ref "U3") (pin "4") (pinfunction "Y_4") (pintype "bidirectional"))
      (node (ref "U6") (pin "22") (pinfunction "DRV_ENN_22") (pintype "bidirectional"))
      (node (ref "U7") (pin "22") (pinfunction "DRV_ENN_22") (pintype "bidirectional"))
      (node (ref "U8") (pin "22") (pinfunction "DRV_ENN_22") (pintype "bidirectional"))
    )
  )
)
